# HANDS_FREE_ControlUnit_V2.net
KiCad netlist of a schematic drawn in Altium Designer
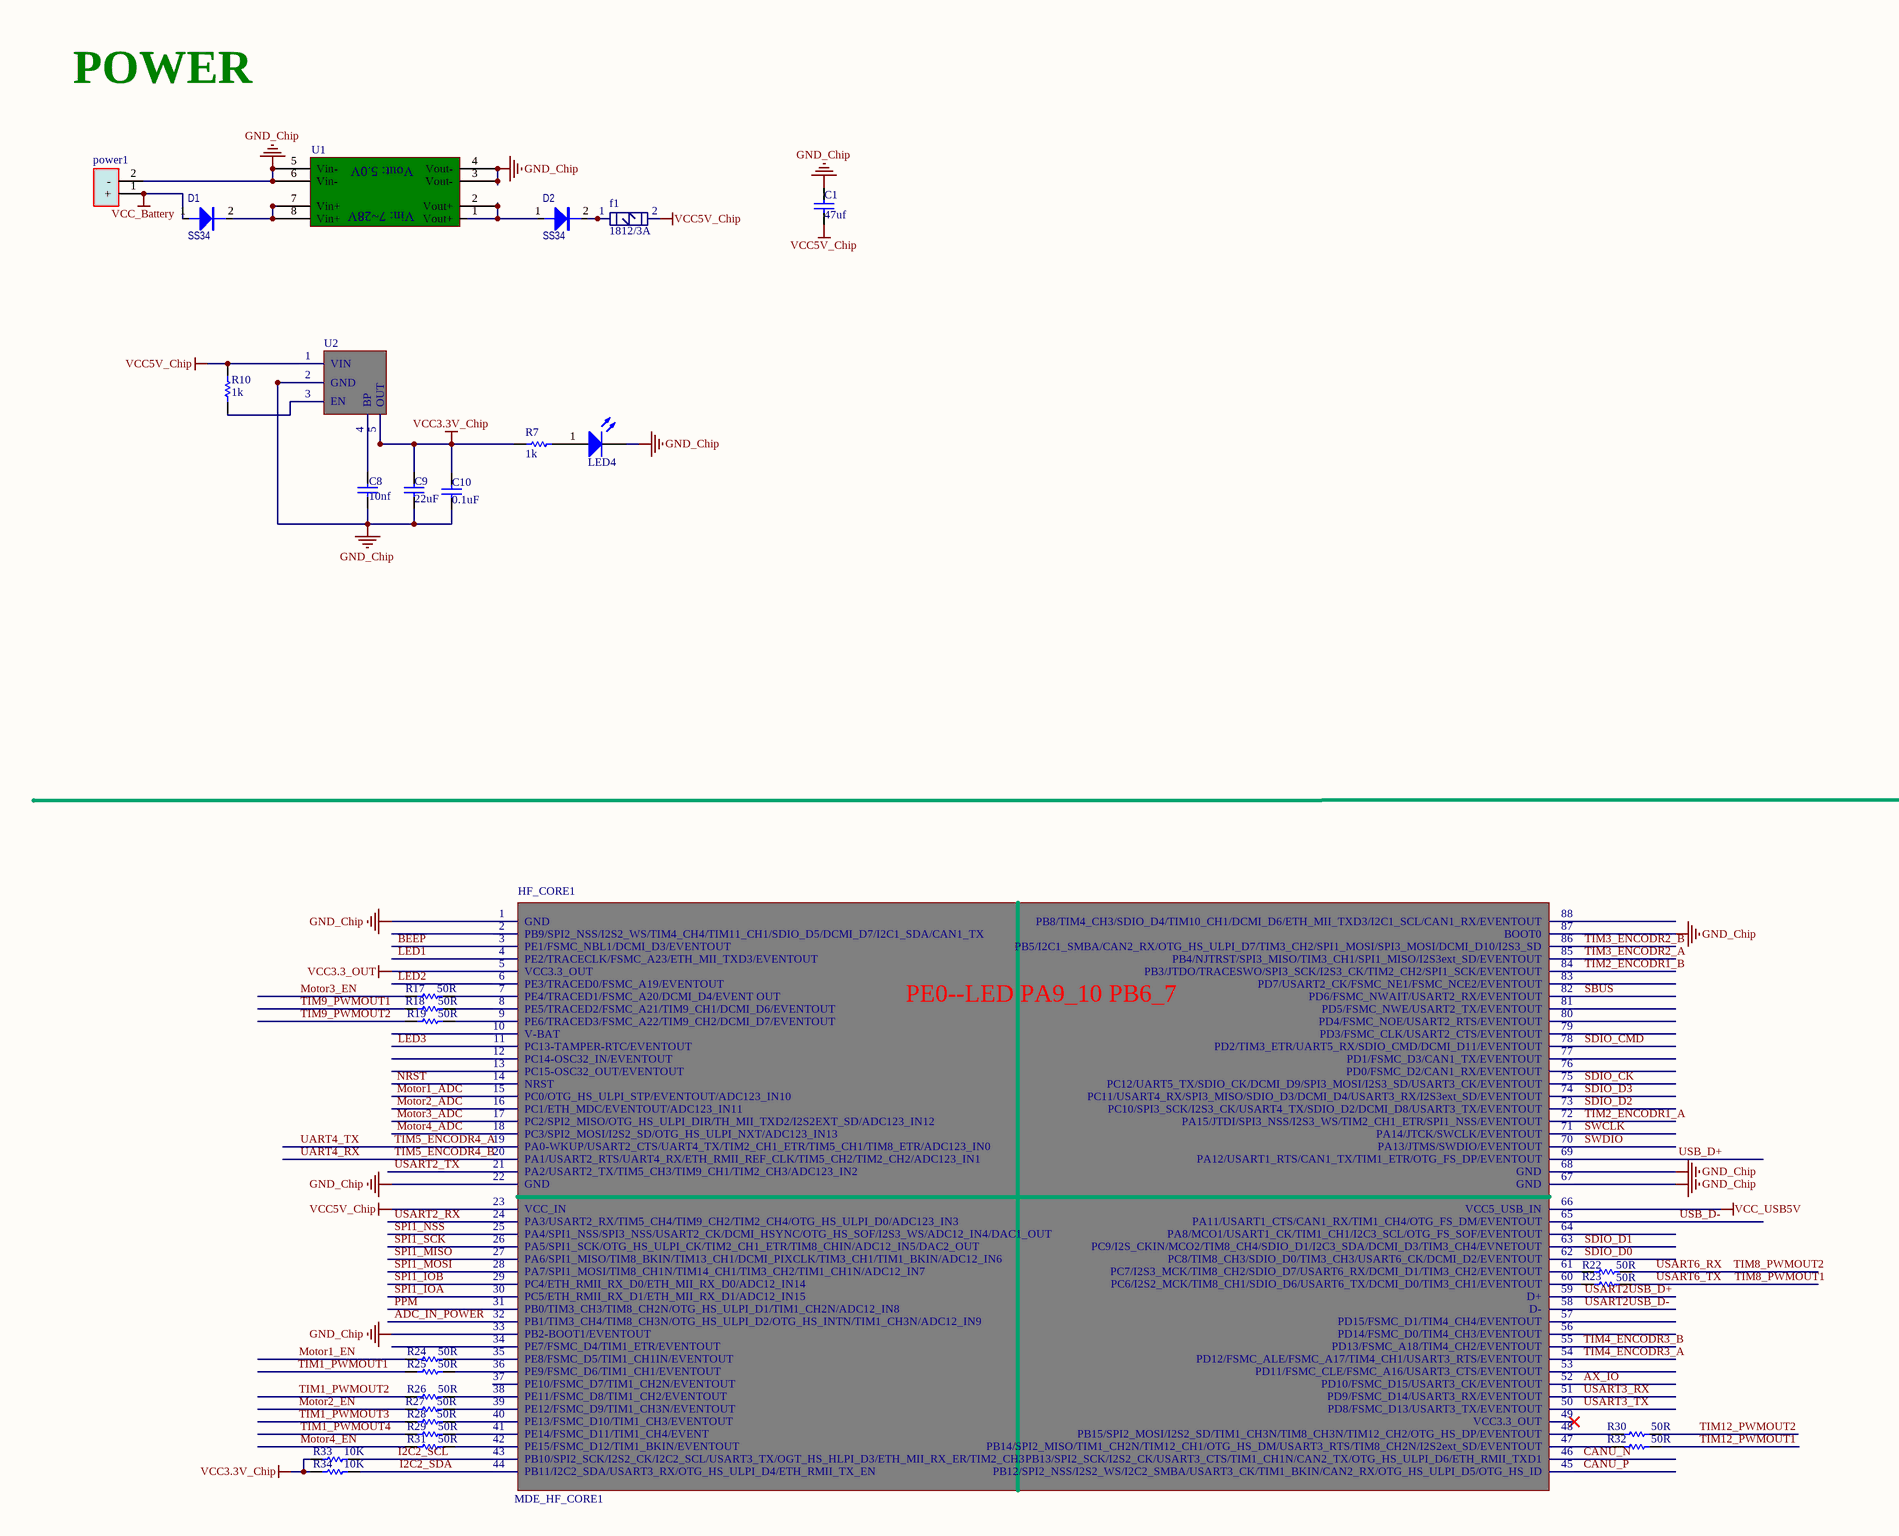
[diagram p0: HANDS_FREE_ControlUnit_V2.SchDoc, top left]
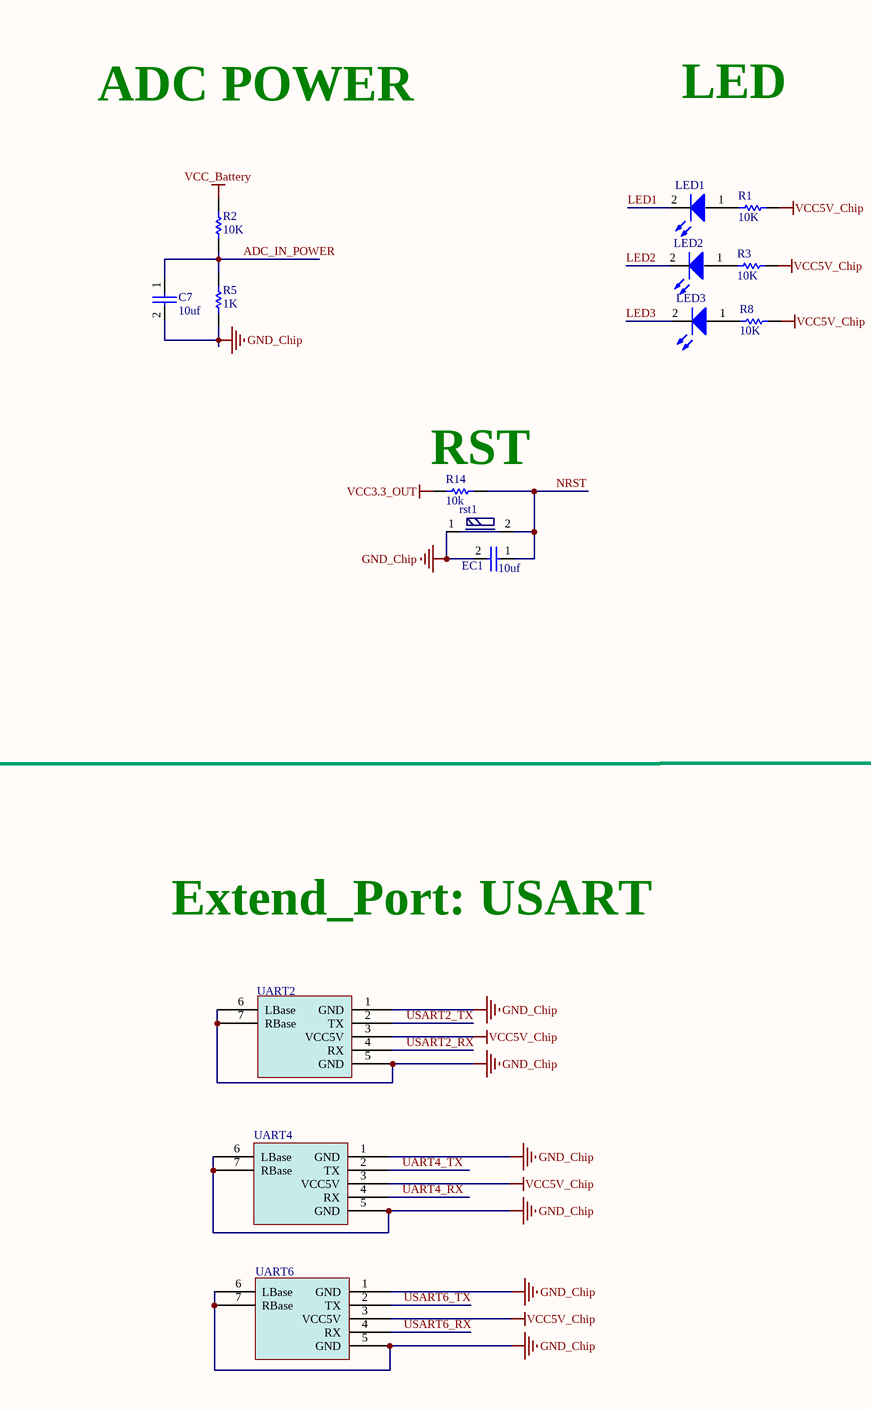
[diagram p1: HANDS_FREE_ControlUnit_V2.SchDoc, top middle]
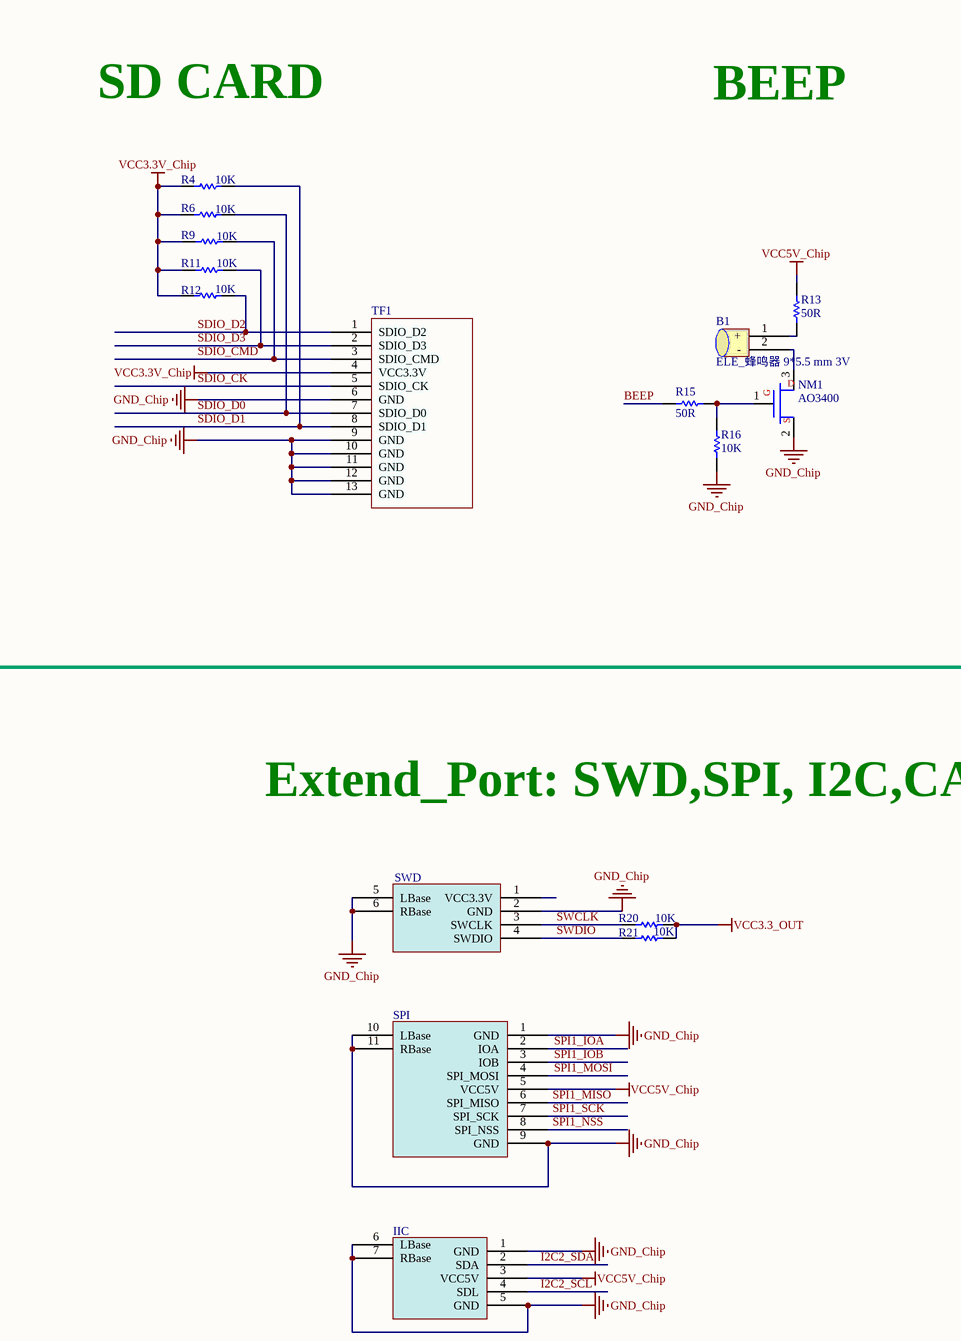
[diagram p2: HANDS_FREE_ControlUnit_V2.SchDoc, top right]
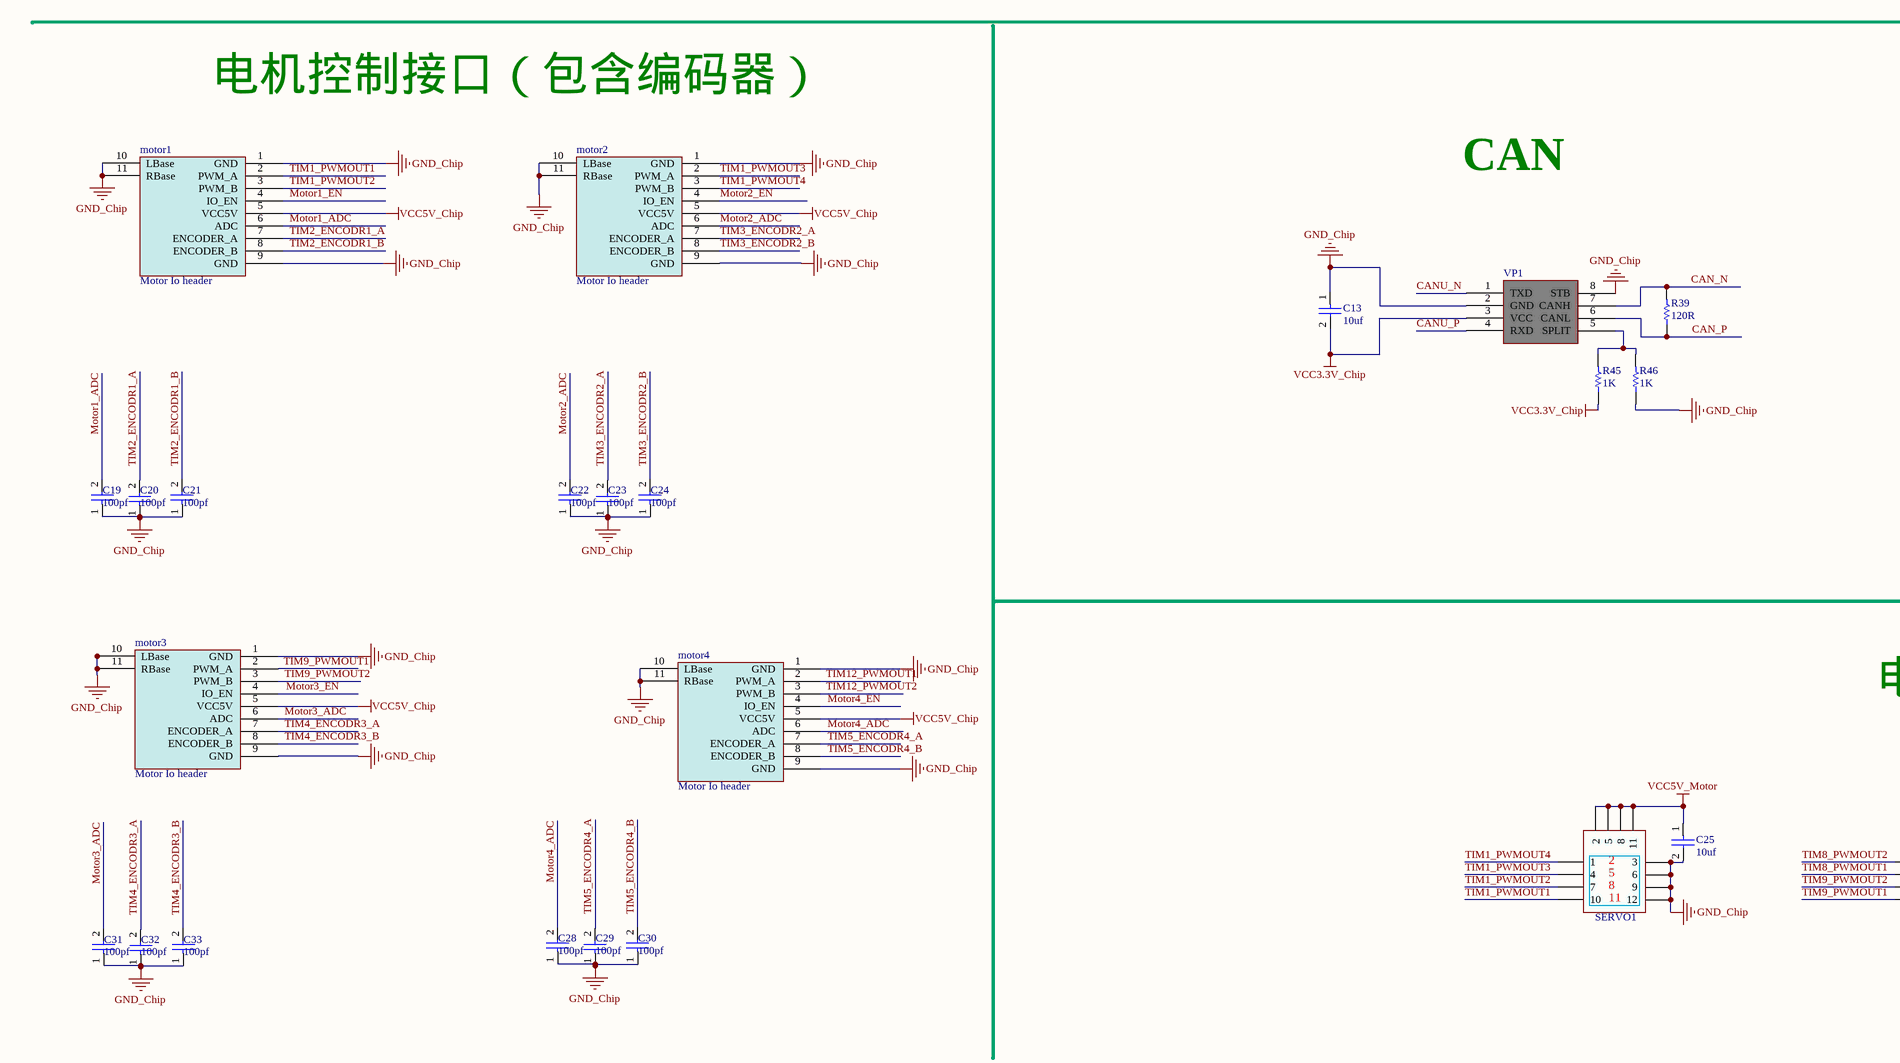
[diagram p3: HANDS_FREE_ControlUnit_V2.SchDoc, bottom left]
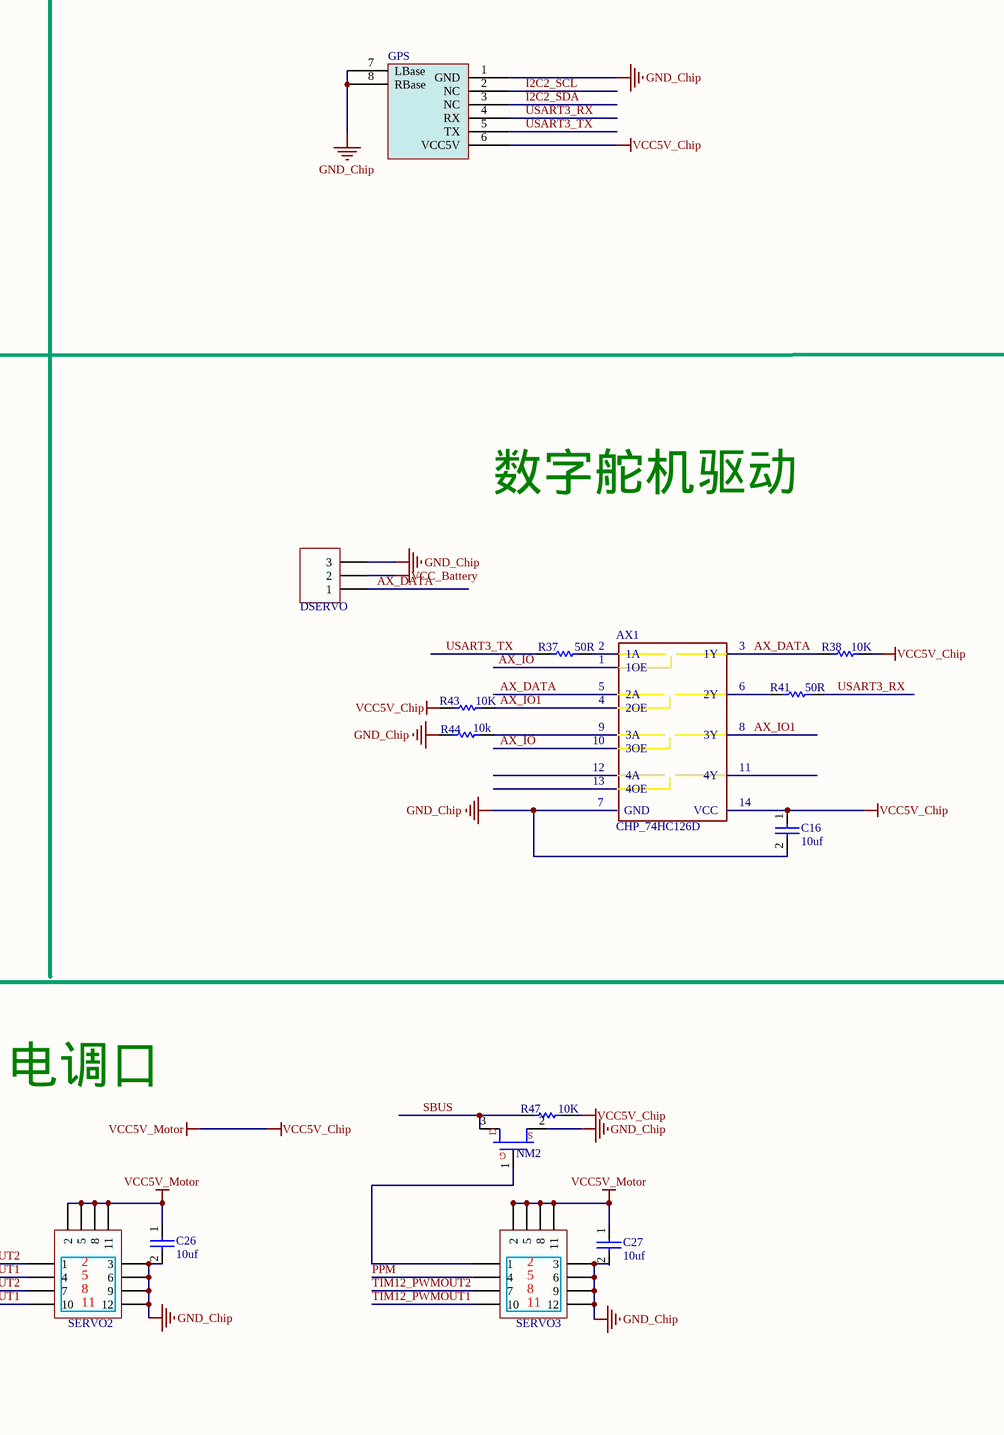
[diagram p4: HANDS_FREE_ControlUnit_V2.SchDoc, bottom middle]
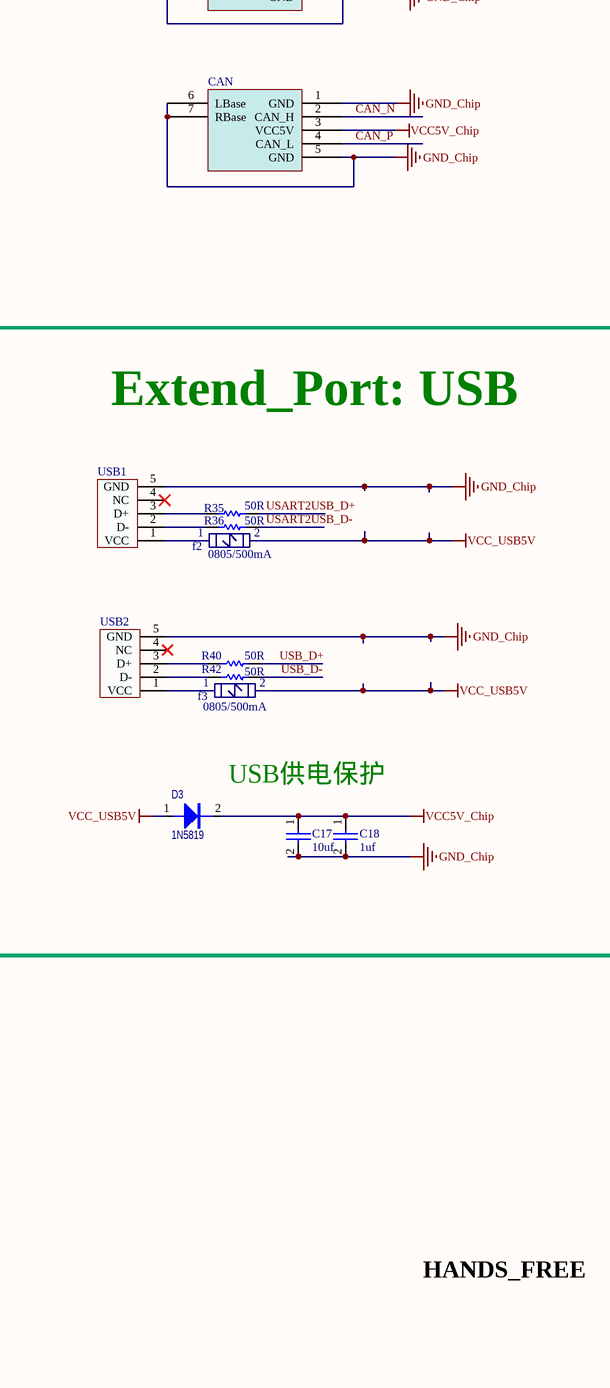
[diagram p5: HANDS_FREE_ControlUnit_V2.SchDoc, bottom right]

(export (version "E")
  (design (tool "Eeschema 10.0.6"))
  (components
    (comp (ref "AX1")
      (value "CHP_74HC126D")
      (footprint "CHP_SOP_14P")
      (description "4路三态门缓冲器")
      (libsource (lib "HANDS-FREEE-PcbLib-V1.01") (part "CHP_74HC126D"))
    )
    (comp (ref "B1")
      (value "ELE_蜂鸣器 9*5.5 mm 3V")
      (footprint "ELE_蜂鸣器_D_9*5.5")
      (description "直插 蜂鸣器 9mm")
      (libsource (lib "Hands_free") (part "ELE_蜂鸣器 9*5.5 mm 3V"))
    )
    (comp (ref "C1") (value "47uf") (footprint "ELE_1206_P") (libsource (lib "My lib") (part "Cap")))
    (comp (ref "C7")
      (value "10uf")
      (footprint "ELE_0603_P")
      (description "贴片 电容100pf 0603")
      (libsource (lib "Hands_free") (part "ELE_Standard_Cap100pf"))
    )
    (comp (ref "C8") (value "10nf") (footprint "ELE_0603_P") (libsource (lib "My lib") (part "Cap")))
    (comp (ref "C9") (value "22uF") (footprint "ELE_0603_P") (libsource (lib "My lib") (part "Cap")))
    (comp (ref "C10") (value "0.1uF") (footprint "ELE_0603_P") (libsource (lib "My lib") (part "Cap")))
    (comp (ref "C13")
      (value "10uf")
      (footprint "ELE_0603_P")
      (description "贴片 电容10uf 0603")
      (libsource (lib "Hands_free") (part "ELE_Standard_Cap10uf"))
    )
    (comp (ref "C16")
      (value "10uf")
      (footprint "ELE_0603_P")
      (description "贴片 电容10uf 0603")
      (libsource (lib "Hands_free") (part "ELE_Standard_Cap10uf"))
    )
    (comp (ref "C17")
      (value "10uf")
      (footprint "ELE_0603_P")
      (description "贴片 电容10uf 0603")
      (libsource (lib "Hands_free") (part "ELE_Standard_Cap10uf"))
    )
    (comp (ref "C18")
      (value "1uf")
      (footprint "ELE_0603_P")
      (description "贴片 电容1uf 0603")
      (libsource (lib "Hands_free") (part "ELE_Standard_Cap1uf"))
    )
    (comp (ref "C19")
      (value "100pf")
      (footprint "ELE_0603_P")
      (description "贴片 电容100pf 0603")
      (libsource (lib "Hands_free") (part "ELE_Standard_Cap100pf"))
    )
    (comp (ref "C20")
      (value "100pf")
      (footprint "ELE_0603_P")
      (description "贴片 电容100pf 0603")
      (libsource (lib "Hands_free") (part "ELE_Standard_Cap100pf"))
    )
    (comp (ref "C21")
      (value "100pf")
      (footprint "ELE_0603_P")
      (description "贴片 电容100pf 0603")
      (libsource (lib "Hands_free") (part "ELE_Standard_Cap100pf"))
    )
    (comp (ref "C22")
      (value "100pf")
      (footprint "ELE_0603_P")
      (description "贴片 电容100pf 0603")
      (libsource (lib "Hands_free") (part "ELE_Standard_Cap100pf"))
    )
    (comp (ref "C23")
      (value "100pf")
      (footprint "ELE_0603_P")
      (description "贴片 电容100pf 0603")
      (libsource (lib "Hands_free") (part "ELE_Standard_Cap100pf"))
    )
    (comp (ref "C24")
      (value "100pf")
      (footprint "ELE_0603_P")
      (description "贴片 电容100pf 0603")
      (libsource (lib "Hands_free") (part "ELE_Standard_Cap100pf"))
    )
    (comp (ref "C25")
      (value "10uf")
      (footprint "ELE_0603_P")
      (description "贴片 电容10uf 0603")
      (libsource (lib "Hands_free") (part "ELE_Standard_Cap10uf"))
    )
    (comp (ref "C26")
      (value "10uf")
      (footprint "ELE_0603_P")
      (description "贴片 电容10uf 0603")
      (libsource (lib "Hands_free") (part "ELE_Standard_Cap10uf"))
    )
    (comp (ref "C27")
      (value "10uf")
      (footprint "ELE_0603_P")
      (description "贴片 电容10uf 0603")
      (libsource (lib "Hands_free") (part "ELE_Standard_Cap10uf"))
    )
    (comp (ref "C28")
      (value "100pf")
      (footprint "ELE_0603_P")
      (description "贴片 电容100pf 0603")
      (libsource (lib "Hands_free") (part "ELE_Standard_Cap100pf"))
    )
    (comp (ref "C29")
      (value "100pf")
      (footprint "ELE_0603_P")
      (description "贴片 电容100pf 0603")
      (libsource (lib "Hands_free") (part "ELE_Standard_Cap100pf"))
    )
    (comp (ref "C30")
      (value "100pf")
      (footprint "ELE_0603_P")
      (description "贴片 电容100pf 0603")
      (libsource (lib "Hands_free") (part "ELE_Standard_Cap100pf"))
    )
    (comp (ref "C31")
      (value "100pf")
      (footprint "ELE_0603_P")
      (description "贴片 电容100pf 0603")
      (libsource (lib "Hands_free") (part "ELE_Standard_Cap100pf"))
    )
    (comp (ref "C32")
      (value "100pf")
      (footprint "ELE_0603_P")
      (description "贴片 电容100pf 0603")
      (libsource (lib "Hands_free") (part "ELE_Standard_Cap100pf"))
    )
    (comp (ref "C33")
      (value "100pf")
      (footprint "ELE_0603_P")
      (description "贴片 电容100pf 0603")
      (libsource (lib "Hands_free") (part "ELE_Standard_Cap100pf"))
    )
    (comp (ref "CAN")
      (value "HANDS_FREE_IMU")
      (footprint "HDR_Molex_PH_1.25_5P")
      (libsource (lib "Hands_free") (part "HANDS_FREE_IMU"))
    )
    (comp (ref "D1")
      (value "SS34")
      (footprint "ELE_D1206")
      (description "贴片 二极管 SS34/SS54")
      (libsource (lib "Hands_free") (part "ELE_Standard_Diode_1206"))
    )
    (comp (ref "D2")
      (value "SS34")
      (footprint "ELE_D1206")
      (description "贴片 二极管 SS34/SS54")
      (libsource (lib "Hands_free") (part "ELE_Standard_Diode_1206"))
    )
    (comp (ref "D3")
      (value "1N5819")
      (footprint "ELE_SOD-323")
      (description "贴片 二极管 SOD323")
      (libsource (lib "Hands_free") (part "ELE_Standard_Diode_SOD323"))
    )
    (comp (ref "DSERVO")
      (value "HDR_Header_1*3")
      (footprint "HDR_数字舵机接口_D")
      (fields (field (name "PUBLISHER") "Altium Limited"))
      (libsource (lib "Hands_free") (part "HDR_Header_1*3"))
    )
    (comp (ref "EC1")
      (value "10uf")
      (footprint "ELE_0603_P")
      (description "贴片 电容100pf 0603")
      (libsource (lib "Hands_free") (part "ELE_Standard_Cap100pf"))
    )
    (comp (ref "f1")
      (value "1812/3A")
      (footprint "ELE_FUZE_1812")
      (description "贴片保险丝 1812 3A")
      (libsource (lib "Hands_free") (part "ELE_Standard_Fuze_1812/3A"))
    )
    (comp (ref "f2")
      (value "0805/500mA")
      (footprint "ELE_FUZE_0805")
      (description "贴片保险丝 0805 500mA")
      (libsource (lib "Hands_free") (part "ELE_Standard_Fuze_0805/500mA"))
    )
    (comp (ref "f3")
      (value "0805/500mA")
      (footprint "ELE_FUZE_0805")
      (description "贴片保险丝 0805 500mA")
      (libsource (lib "Hands_free") (part "ELE_Standard_Fuze_0805/500mA"))
    )
    (comp (ref "GPS")
      (value "HANDS_FREE_GPS")
      (footprint "HDR_Molex_PH_1.25_6P")
      (libsource (lib "Hands_free") (part "HANDS_FREE_GPS"))
    )
    (comp (ref "HF_CORE1")
      (value "MDE_HF_CORE1")
      (footprint "MDE_HF_CORE1")
      (description "HANDS FREE核心板1代")
      (libsource (lib "HANDS-FREEE-PcbLib-V1.11") (part "MDE_HF_CORE1"))
    )
    (comp (ref "IIC")
      (value "HANDS_FREE_IIC")
      (footprint "HDR_Molex_PH_1.25_5P")
      (libsource (lib "Hands_free") (part "HANDS_FREE_IIC"))
    )
    (comp (ref "LED1")
      (value "ELE_LED")
      (footprint "ELE_0603极性_P")
      (description "发光二极管 0603")
      (fields (field (name "PUBLISHER") "Altium Limited"))
      (libsource (lib "HANDS-FREEE-PcbLib-V1.11") (part "ELE_LED"))
    )
    (comp (ref "LED2")
      (value "ELE_LED")
      (footprint "ELE_0603极性_P")
      (description "发光二极管 0603")
      (fields (field (name "PUBLISHER") "Altium Limited"))
      (libsource (lib "HANDS-FREEE-PcbLib-V1.11") (part "ELE_LED"))
    )
    (comp (ref "LED3")
      (value "ELE_LED")
      (footprint "ELE_0603极性_P")
      (description "发光二极管 0603")
      (fields (field (name "PUBLISHER") "Altium Limited"))
      (libsource (lib "HANDS-FREEE-PcbLib-V1.11") (part "ELE_LED"))
    )
    (comp (ref "LED4") (value "Led_sp") (footprint "ELE_0603极性_P") (libsource (lib "My lib") (part "Led_sp")))
    (comp (ref "motor1")
      (value "Motor Io header")
      (footprint "HDR_Molex_PH_1.25_9P")
      (description "卧贴 molex 1.25间距 9P接口")
      (libsource (lib "Hands_free") (part "HANDS_FREE_MOTOR"))
    )
    (comp (ref "motor2")
      (value "Motor Io header")
      (footprint "HDR_Molex_PH_1.25_9P")
      (description "卧贴 molex 1.25间距 9P接口")
      (libsource (lib "Hands_free") (part "HANDS_FREE_MOTOR"))
    )
    (comp (ref "motor3")
      (value "Motor Io header")
      (footprint "HDR_Molex_PH_1.25_9P")
      (description "卧贴 molex 1.25间距 9P接口")
      (libsource (lib "Hands_free") (part "HANDS_FREE_MOTOR"))
    )
    (comp (ref "motor4")
      (value "Motor Io header")
      (footprint "HDR_Molex_PH_1.25_9P")
      (description "卧贴 molex 1.25间距 9P接口")
      (libsource (lib "Hands_free") (part "HANDS_FREE_MOTOR"))
    )
    (comp (ref "NM1")
      (value "AO3400")
      (footprint "CHP_SOT23_P_3P")
      (description "贴片 NMOS管 SOT23")
      (fields (field (name "PUBLISHER") "Altium Limited"))
      (libsource (lib "Hands_free") (part "ELE_NMOS_1"))
    )
    (comp (ref "NM2")
      (value "AO3400")
      (footprint "CHP_SOT23_P_3P")
      (description "贴片 NMOS管 SOT23")
      (fields (field (name "PUBLISHER") "Altium Limited"))
      (libsource (lib "Hands_free") (part "ELE_NMOS_1"))
    )
    (comp (ref "power1")
      (value "HDR_Header_Power_2P")
      (footprint "HDR_MOLEX_CANMX3.0_DH_2P")
      (libsource (lib "HANDS-FREEE-PcbLib-V1.00") (part "HDR_Header_Power_2P"))
    )
    (comp (ref "R1")
      (value "10K")
      (footprint "ELE_0603_P")
      (description "贴片 电阻1K欧 0603")
      (libsource (lib "Hands_free") (part "ELE_Standard_R1K"))
    )
    (comp (ref "R2")
      (value "10K")
      (footprint "ELE_0603_P")
      (description "贴片 电阻1K欧 0603")
      (libsource (lib "Hands_free") (part "ELE_Standard_R1K"))
    )
    (comp (ref "R3")
      (value "10K")
      (footprint "ELE_0603_P")
      (description "贴片 电阻1K欧 0603")
      (libsource (lib "Hands_free") (part "ELE_Standard_R1K"))
    )
    (comp (ref "R4")
      (value "10K")
      (footprint "ELE_0603_P")
      (description "贴片 电阻10K欧 0603")
      (libsource (lib "Hands_free") (part "ELE_Standard_R10K"))
    )
    (comp (ref "R5")
      (value "1K")
      (footprint "ELE_0603_P")
      (description "贴片 电阻10K欧 0603")
      (libsource (lib "Hands_free") (part "ELE_Standard_R10K"))
    )
    (comp (ref "R6")
      (value "10K")
      (footprint "ELE_0603_P")
      (description "贴片 电阻10K欧 0603")
      (libsource (lib "Hands_free") (part "ELE_Standard_R10K"))
    )
    (comp (ref "R7")
      (value "1k")
      (footprint "ELE_0603_P")
      (description "贴片 电阻50欧 0603")
      (libsource (lib "Hands_free") (part "ELE_Standard_R50R"))
    )
    (comp (ref "R8")
      (value "10K")
      (footprint "ELE_0603_P")
      (description "贴片 电阻1K欧 0603")
      (libsource (lib "Hands_free") (part "ELE_Standard_R1K"))
    )
    (comp (ref "R9")
      (value "10K")
      (footprint "ELE_0603_P")
      (description "贴片 电阻10K欧 0603")
      (libsource (lib "Hands_free") (part "ELE_Standard_R10K"))
    )
    (comp (ref "R10")
      (value "1k")
      (footprint "ELE_0603_P")
      (description "贴片 电阻50欧 0603")
      (libsource (lib "Hands_free") (part "ELE_Standard_R50R"))
    )
    (comp (ref "R11")
      (value "10K")
      (footprint "ELE_0603_P")
      (description "贴片 电阻10K欧 0603")
      (libsource (lib "Hands_free") (part "ELE_Standard_R10K"))
    )
    (comp (ref "R12")
      (value "10K")
      (footprint "ELE_0603_P")
      (description "贴片 电阻10K欧 0603")
      (libsource (lib "Hands_free") (part "ELE_Standard_R10K"))
    )
    (comp (ref "R13")
      (value "50R")
      (footprint "ELE_0603_P")
      (description "贴片 电阻10K欧 0603")
      (libsource (lib "Hands_free") (part "ELE_Standard_R10K"))
    )
    (comp (ref "R14")
      (value "10k")
      (footprint "ELE_0603_P")
      (description "贴片 电阻50欧 0603")
      (libsource (lib "Hands_free") (part "ELE_Standard_R50R"))
    )
    (comp (ref "R15")
      (value "50R")
      (footprint "ELE_0603_P")
      (description "贴片 电阻50欧 0603")
      (libsource (lib "Hands_free") (part "ELE_Standard_R50R"))
    )
    (comp (ref "R16")
      (value "10K")
      (footprint "ELE_0603_P")
      (description "贴片 电阻10K欧 0603")
      (libsource (lib "Hands_free") (part "ELE_Standard_R10K"))
    )
    (comp (ref "R17")
      (value "50R")
      (footprint "ELE_0603_P")
      (description "贴片 电阻50欧 0603")
      (libsource (lib "Hands_free") (part "ELE_Standard_R50R"))
    )
    (comp (ref "R18")
      (value "50R")
      (footprint "ELE_0603_P")
      (description "贴片 电阻50欧 0603")
      (libsource (lib "Hands_free") (part "ELE_Standard_R50R"))
    )
    (comp (ref "R19")
      (value "50R")
      (footprint "ELE_0603_P")
      (description "贴片 电阻50欧 0603")
      (libsource (lib "Hands_free") (part "ELE_Standard_R50R"))
    )
    (comp (ref "R20")
      (value "10K")
      (footprint "ELE_0603_P")
      (description "贴片 电阻10K欧 0603")
      (libsource (lib "Hands_free") (part "ELE_Standard_R10K"))
    )
    (comp (ref "R21")
      (value "10K")
      (footprint "ELE_0603_P")
      (description "贴片 电阻10K欧 0603")
      (libsource (lib "Hands_free") (part "ELE_Standard_R10K"))
    )
    (comp (ref "R22")
      (value "50R")
      (footprint "ELE_0603_P")
      (description "贴片 电阻50欧 0603")
      (libsource (lib "Hands_free") (part "ELE_Standard_R50R"))
    )
    (comp (ref "R23")
      (value "50R")
      (footprint "ELE_0603_P")
      (description "贴片 电阻50欧 0603")
      (libsource (lib "Hands_free") (part "ELE_Standard_R50R"))
    )
    (comp (ref "R24")
      (value "50R")
      (footprint "ELE_0603_P")
      (description "贴片 电阻50欧 0603")
      (libsource (lib "Hands_free") (part "ELE_Standard_R50R"))
    )
    (comp (ref "R25")
      (value "50R")
      (footprint "ELE_0603_P")
      (description "贴片 电阻50欧 0603")
      (libsource (lib "Hands_free") (part "ELE_Standard_R50R"))
    )
    (comp (ref "R26")
      (value "50R")
      (footprint "ELE_0603_P")
      (description "贴片 电阻50欧 0603")
      (libsource (lib "Hands_free") (part "ELE_Standard_R50R"))
    )
    (comp (ref "R27")
      (value "50R")
      (footprint "ELE_0603_P")
      (description "贴片 电阻50欧 0603")
      (libsource (lib "Hands_free") (part "ELE_Standard_R50R"))
    )
    (comp (ref "R28")
      (value "50R")
      (footprint "ELE_0603_P")
      (description "贴片 电阻50欧 0603")
      (libsource (lib "Hands_free") (part "ELE_Standard_R50R"))
    )
    (comp (ref "R29")
      (value "50R")
      (footprint "ELE_0603_P")
      (description "贴片 电阻50欧 0603")
      (libsource (lib "Hands_free") (part "ELE_Standard_R50R"))
    )
    (comp (ref "R30")
      (value "50R")
      (footprint "ELE_0603_P")
      (description "贴片 电阻50欧 0603")
      (libsource (lib "Hands_free") (part "ELE_Standard_R50R"))
    )
    (comp (ref "R31")
      (value "50R")
      (footprint "ELE_0603_P")
      (description "贴片 电阻50欧 0603")
      (libsource (lib "Hands_free") (part "ELE_Standard_R50R"))
    )
    (comp (ref "R32")
      (value "50R")
      (footprint "ELE_0603_P")
      (description "贴片 电阻50欧 0603")
      (libsource (lib "Hands_free") (part "ELE_Standard_R50R"))
    )
    (comp (ref "R33")
      (value "10K")
      (footprint "ELE_0603_P")
      (description "贴片 电阻10K欧 0603")
      (libsource (lib "Hands_free") (part "ELE_Standard_R10K"))
    )
    (comp (ref "R34")
      (value "10K")
      (footprint "ELE_0603_P")
      (description "贴片 电阻10K欧 0603")
      (libsource (lib "Hands_free") (part "ELE_Standard_R10K"))
    )
    (comp (ref "R35")
      (value "50R")
      (footprint "ELE_0603_P")
      (description "贴片 电阻50欧 0603")
      (libsource (lib "Hands_free") (part "ELE_Standard_R50R"))
    )
    (comp (ref "R36")
      (value "50R")
      (footprint "ELE_0603_P")
      (description "贴片 电阻50欧 0603")
      (libsource (lib "Hands_free") (part "ELE_Standard_R50R"))
    )
    (comp (ref "R37")
      (value "50R")
      (footprint "ELE_0603_P")
      (description "贴片 电阻50欧 0603")
      (libsource (lib "Hands_free") (part "ELE_Standard_R50R"))
    )
    (comp (ref "R38")
      (value "10K")
      (footprint "ELE_0603_P")
      (description "贴片 电阻10K欧 0603")
      (libsource (lib "Hands_free") (part "10K"))
    )
    (comp (ref "R39")
      (value "120R")
      (footprint "ELE_0603_P")
      (description "贴片 电阻120欧 0603")
      (libsource (lib "Hands_free") (part "ELE_Standard_R120R"))
    )
    (comp (ref "R40")
      (value "50R")
      (footprint "ELE_0603_P")
      (description "贴片 电阻50欧 0603")
      (libsource (lib "Hands_free") (part "ELE_Standard_R50R"))
    )
    (comp (ref "R41")
      (value "50R")
      (footprint "ELE_0603_P")
      (description "贴片 电阻50欧 0603")
      (libsource (lib "Hands_free") (part "ELE_Standard_R50R"))
    )
    (comp (ref "R42")
      (value "50R")
      (footprint "ELE_0603_P")
      (description "贴片 电阻50欧 0603")
      (libsource (lib "Hands_free") (part "ELE_Standard_R50R"))
    )
    (comp (ref "R43")
      (value "10K")
      (footprint "ELE_0603_P")
      (description "贴片 电阻50欧 0603")
      (libsource (lib "Hands_free") (part "ELE_Standard_R50R"))
    )
    (comp (ref "R44")
      (value "10k")
      (footprint "ELE_0603_P")
      (description "贴片 电阻50欧 0603")
      (libsource (lib "Hands_free") (part "ELE_Standard_R50R"))
    )
    (comp (ref "R45")
      (value "1K")
      (footprint "ELE_0603_P")
      (description "贴片 电阻10K欧 0603")
      (libsource (lib "Hands_free") (part "ELE_Standard_R10K"))
    )
    (comp (ref "R46")
      (value "1K")
      (footprint "ELE_0603_P")
      (description "贴片 电阻10K欧 0603")
      (libsource (lib "Hands_free") (part "ELE_Standard_R10K"))
    )
    (comp (ref "R47")
      (value "10K")
      (footprint "ELE_0603_P")
      (description "贴片 电阻10K欧 0603")
      (libsource (lib "Hands_free") (part "ELE_Standard_R10K"))
    )
    (comp (ref "rst1")
      (value "ELE_KEY_1")
      (footprint "ELE_KEY_P")
      (description "贴片 触发开关 2P")
      (libsource (lib "Hands_free") (part "ELE_KEY_1"))
    )
    (comp (ref "SERVO1")
      (value "HDR_Header_4*3")
      (footprint "HDR_Header_2.54/3.0_DV_3*4")
      (description "直插 三排排针")
      (libsource (lib "Hands_free") (part "HDR_Header_4*3"))
    )
    (comp (ref "SERVO2")
      (value "HDR_Header_4*3")
      (footprint "HDR_Header_2.54/3.0_DV_3*4")
      (description "直插 三排排针")
      (libsource (lib "Hands_free") (part "HDR_Header_4*3"))
    )
    (comp (ref "SERVO3")
      (value "HDR_Header_4*3")
      (footprint "HDR_Header_2.54/3.0_DV_3*4")
      (description "直插 三排排针")
      (libsource (lib "Hands_free") (part "HDR_Header_4*3"))
    )
    (comp (ref "SPI")
      (value "HANDS_FREE_SPI")
      (footprint "HDR_Molex_PH_1.25_9P")
      (libsource (lib "Hands_free") (part "HANDS_FREE_SPI"))
    )
    (comp (ref "SWD")
      (value "HANDS_FREE_SWD")
      (footprint "HDR_Molex_PH_1.25_4P")
      (libsource (lib "Hands_free") (part "HANDS_FREE_SWD"))
    )
    (comp (ref "TF1")
      (value "HDR_MicroTFCARD")
      (footprint "HDR_TFCARD_P")
      (libsource (lib "Hands_free") (part "HDR_MicroTFCARD"))
    )
    (comp (ref "U1")
      (value "MDE_DM02-5.0")
      (footprint "MDE_DM02-5.0")
      (libsource (lib "Hands_free") (part "MDE_DM02-5.0"))
    )
    (comp (ref "U2")
      (value "~")
      (footprint "CHP_SOT23_P_5P")
      (description "贴片 RT9193稳压芯片 SOT23_5P 3.3v")
      (libsource (lib "Hands_free") (part "CHP_RT9193"))
    )
    (comp (ref "UART2")
      (value "HANDS_FREE_USART")
      (footprint "HDR_Molex_PH_1.25_5P")
      (libsource (lib "Hands_free") (part "HANDS_FREE_USART"))
    )
    (comp (ref "UART4")
      (value "HANDS_FREE_USART")
      (footprint "HDR_Molex_PH_1.25_5P")
      (libsource (lib "Hands_free") (part "HANDS_FREE_USART"))
    )
    (comp (ref "UART6")
      (value "HANDS_FREE_USART")
      (footprint "HDR_Molex_PH_1.25_5P")
      (libsource (lib "Hands_free") (part "HANDS_FREE_USART"))
    )
    (comp (ref "USB1")
      (value "USBMICRO")
      (footprint "HDR_USB_Micro2")
      (libsource (lib "Hands_free") (part "HDR_USBMINI"))
    )
    (comp (ref "USB2")
      (value "USBMICRO")
      (footprint "HDR_USB_Micro2")
      (libsource (lib "Hands_free") (part "HDR_USBMINI"))
    )
    (comp (ref "VP1")
      (value "CHP_VP230_P")
      (footprint "CHP_VP230_P")
      (libsource (lib "Hands_free") (part "CHP_VP230_P"))
    )
  )
  (nets
    (net (code "1") (name "/ADC_IN_POWER") (class "Default")
      (node (ref "C7") (pin "1") (pintype "passive"))
      (node (ref "HF_CORE1") (pin "32") (pinfunction "PB1/TIM3_CH4/TIM8_CH3N/OTG_HS_ULPI_D2/OTG_HS_INTN/TIM1_CH3N/ADC12_IN9_32") (pintype "passive"))
      (node (ref "R2") (pin "2") (pinfunction "2_2") (pintype "passive"))
      (node (ref "R5") (pin "1") (pinfunction "1_1") (pintype "passive"))
    )
    (net (code "2") (name "/AX_DATA") (class "Default")
      (node (ref "AX1") (pin "3") (pinfunction "1Y_3") (pintype "passive"))
      (node (ref "AX1") (pin "5") (pinfunction "2A_5") (pintype "passive"))
      (node (ref "DSERVO") (pin "1") (pinfunction "1_1") (pintype "passive"))
      (node (ref "R38") (pin "2") (pinfunction "2_2") (pintype "passive"))
    )
    (net (code "3") (name "/AX_IO") (class "Default")
      (node (ref "AX1") (pin "1") (pinfunction "1OE_1") (pintype "passive"))
      (node (ref "AX1") (pin "10") (pinfunction "3OE_10") (pintype "passive"))
      (node (ref "HF_CORE1") (pin "52") (pinfunction "PD10/FSMC_D15/USART3_CK/EVENTOUT_52") (pintype "passive"))
    )
    (net (code "4") (name "/AX_IO1") (class "Default")
      (node (ref "AX1") (pin "4") (pinfunction "2OE_4") (pintype "passive"))
      (node (ref "AX1") (pin "8") (pinfunction "3Y_8") (pintype "passive"))
      (node (ref "R43") (pin "1") (pinfunction "1_1") (pintype "passive"))
    )
    (net (code "5") (name "/BEEP") (class "Default")
      (node (ref "HF_CORE1") (pin "3") (pinfunction "PE1/FSMC_NBL1/DCMI_D3/EVENTOUT_3") (pintype "passive"))
      (node (ref "R15") (pin "2") (pinfunction "2_2") (pintype "passive"))
    )
    (net (code "6") (name "/CANU_N") (class "Default")
      (node (ref "HF_CORE1") (pin "46") (pinfunction "PB13/SPI2_SCK/I2S2_CK/USART3_CTS/TIM1_CH1N/CAN2_TX/OTG_HS_ULPI_D6/ETH_RMII_TXD1_46") (pintype "passive"))
      (node (ref "VP1") (pin "1") (pinfunction "TXD_1") (pintype "passive"))
    )
    (net (code "7") (name "/CANU_P") (class "Default")
      (node (ref "HF_CORE1") (pin "45") (pinfunction "PB12/SPI2_NSS/I2S2_WS/I2C2_SMBA/USART3_CK/TIM1_BKIN/CAN2_RX/OTG_HS_ULPI_D5/OTG_HS_ID_45") (pintype "passive"))
      (node (ref "VP1") (pin "4") (pinfunction "RXD_4") (pintype "passive"))
    )
    (net (code "8") (name "/CAN_N") (class "Default")
      (node (ref "CAN") (pin "2") (pinfunction "CAN_H_2") (pintype "passive"))
      (node (ref "R39") (pin "1") (pinfunction "1_1") (pintype "passive"))
      (node (ref "VP1") (pin "7") (pinfunction "CANH_7") (pintype "passive"))
    )
    (net (code "9") (name "/CAN_P") (class "Default")
      (node (ref "CAN") (pin "4") (pinfunction "CAN_L_4") (pintype "passive"))
      (node (ref "R39") (pin "2") (pinfunction "2_2") (pintype "passive"))
      (node (ref "VP1") (pin "6") (pinfunction "CANL_6") (pintype "passive"))
    )
    (net (code "10") (name "/I2C2_SCL") (class "Default")
      (node (ref "GPS") (pin "2") (pinfunction "NC_2") (pintype "passive"))
      (node (ref "HF_CORE1") (pin "43") (pinfunction "PB10/SPI2_SCK/I2S2_CK/I2C2_SCL/USART3_TX/OGT_HS_HLPI_D3/ETH_MII_RX_ER/TIM2_CH3_43") (pintype "passive"))
      (node (ref "IIC") (pin "4") (pinfunction "SDL_4") (pintype "passive"))
      (node (ref "R33") (pin "1") (pinfunction "1_1") (pintype "passive"))
    )
    (net (code "11") (name "/I2C2_SDA") (class "Default")
      (node (ref "GPS") (pin "3") (pinfunction "NC_3") (pintype "passive"))
      (node (ref "HF_CORE1") (pin "44") (pinfunction "PB11/I2C2_SDA/USART3_RX/OTG_HS_ULPI_D4/ETH_RMII_TX_EN_44") (pintype "passive"))
      (node (ref "IIC") (pin "2") (pinfunction "SDA_2") (pintype "passive"))
      (node (ref "R34") (pin "1") (pinfunction "1_1") (pintype "passive"))
    )
    (net (code "12") (name "/LED1") (class "Default")
      (node (ref "HF_CORE1") (pin "4") (pinfunction "PE2/TRACECLK/FSMC_A23/ETH_MII_TXD3/EVENTOUT_4") (pintype "passive"))
      (node (ref "LED1") (pin "2") (pintype "passive"))
    )
    (net (code "13") (name "/LED2") (class "Default")
      (node (ref "HF_CORE1") (pin "6") (pinfunction "PE3/TRACED0/FSMC_A19/EVENTOUT_6") (pintype "passive"))
      (node (ref "LED2") (pin "2") (pintype "passive"))
    )
    (net (code "14") (name "/LED3") (class "Default")
      (node (ref "HF_CORE1") (pin "11") (pinfunction "PC13-TAMPER-RTC/EVENTOUT_11") (pintype "passive"))
      (node (ref "LED3") (pin "2") (pintype "passive"))
    )
    (net (code "15") (name "/Motor1_ADC") (class "Default")
      (node (ref "C19") (pin "2") (pintype "passive"))
      (node (ref "HF_CORE1") (pin "15") (pinfunction "PC0/OTG_HS_ULPI_STP/EVENTOUT/ADC123_IN10_15") (pintype "passive"))
      (node (ref "motor1") (pin "6") (pinfunction "ADC_6") (pintype "passive"))
    )
    (net (code "16") (name "/Motor1_EN") (class "Default")
      (node (ref "R24") (pin "2") (pinfunction "2_2") (pintype "passive"))
      (node (ref "motor1") (pin "4") (pinfunction "IO_EN_4") (pintype "passive"))
    )
    (net (code "17") (name "/Motor2_ADC") (class "Default")
      (node (ref "C22") (pin "2") (pintype "passive"))
      (node (ref "HF_CORE1") (pin "16") (pinfunction "PC1/ETH_MDC/EVENTOUT/ADC123_IN11_16") (pintype "passive"))
      (node (ref "motor2") (pin "6") (pinfunction "ADC_6") (pintype "passive"))
    )
    (net (code "18") (name "/Motor2_EN") (class "Default")
      (node (ref "R27") (pin "2") (pinfunction "2_2") (pintype "passive"))
      (node (ref "motor2") (pin "4") (pinfunction "IO_EN_4") (pintype "passive"))
    )
    (net (code "19") (name "/Motor3_ADC") (class "Default")
      (node (ref "C31") (pin "2") (pintype "passive"))
      (node (ref "HF_CORE1") (pin "17") (pinfunction "PC2/SPI2_MISO/OTG_HS_ULPI_DIR/TH_MII_TXD2/I2S2EXT_SD/ADC123_IN12_17") (pintype "passive"))
      (node (ref "motor3") (pin "6") (pinfunction "ADC_6") (pintype "passive"))
    )
    (net (code "20") (name "/Motor3_EN") (class "Default")
      (node (ref "R17") (pin "2") (pinfunction "2_2") (pintype "passive"))
      (node (ref "motor3") (pin "4") (pinfunction "IO_EN_4") (pintype "passive"))
    )
    (net (code "21") (name "/Motor4_ADC") (class "Default")
      (node (ref "C28") (pin "2") (pintype "passive"))
      (node (ref "HF_CORE1") (pin "18") (pinfunction "PC3/SPI2_MOSI/I2S2_SD/OTG_HS_ULPI_NXT/ADC123_IN13_18") (pintype "passive"))
      (node (ref "motor4") (pin "6") (pinfunction "ADC_6") (pintype "passive"))
    )
    (net (code "22") (name "/Motor4_EN") (class "Default")
      (node (ref "R31") (pin "2") (pinfunction "2_2") (pintype "passive"))
      (node (ref "motor4") (pin "4") (pinfunction "IO_EN_4") (pintype "passive"))
    )
    (net (code "23") (name "/NRST") (class "Default")
      (node (ref "EC1") (pin "1") (pintype "passive"))
      (node (ref "HF_CORE1") (pin "14") (pinfunction "NRST_14") (pintype "passive"))
      (node (ref "R14") (pin "2") (pinfunction "2_2") (pintype "passive"))
      (node (ref "rst1") (pin "2") (pintype "passive"))
    )
    (net (code "24") (name "/PPM") (class "Default")
      (node (ref "HF_CORE1") (pin "31") (pinfunction "PB0/TIM3_CH3/TIM8_CH2N/OTG_HS_ULPI_D1/TIM1_CH2N/ADC12_IN8_31") (pintype "passive"))
      (node (ref "SERVO3") (pin "4") (pinfunction "4_4") (pintype "passive"))
    )
    (net (code "25") (name "/SBUS") (class "Default")
      (node (ref "HF_CORE1") (pin "82") (pinfunction "PD6/FSMC_NWAIT/USART2_RX/EVENTOUT_82") (pintype "passive"))
      (node (ref "NM2") (pin "3") (pinfunction "D_3") (pintype "passive"))
      (node (ref "R47") (pin "2") (pinfunction "2_2") (pintype "passive"))
    )
    (net (code "26") (name "/SDIO_CK") (class "Default")
      (node (ref "HF_CORE1") (pin "75") (pinfunction "PC12/UART5_TX/SDIO_CK/DCMI_D9/SPI3_MOSI/I2S3_SD/USART3_CK/EVENTOUT_75") (pintype "passive"))
      (node (ref "TF1") (pin "5") (pinfunction "SDIO_CK_5") (pintype "passive"))
    )
    (net (code "27") (name "/SDIO_CMD") (class "Default")
      (node (ref "HF_CORE1") (pin "78") (pinfunction "PD2/TIM3_ETR/UART5_RX/SDIO_CMD/DCMI_D11/EVENTOUT_78") (pintype "passive"))
      (node (ref "R9") (pin "1") (pinfunction "1_1") (pintype "passive"))
      (node (ref "TF1") (pin "3") (pinfunction "SDIO_CMD_3") (pintype "passive"))
    )
    (net (code "28") (name "/SDIO_D0") (class "Default")
      (node (ref "HF_CORE1") (pin "62") (pinfunction "PC8/TIM8_CH3/SDIO_D0/TIM3_CH3/USART6_CK/DCMI_D2/EVENTOUT_62") (pintype "passive"))
      (node (ref "R6") (pin "1") (pinfunction "1_1") (pintype "passive"))
      (node (ref "TF1") (pin "7") (pinfunction "SDIO_D0_7") (pintype "passive"))
    )
    (net (code "29") (name "/SDIO_D1") (class "Default")
      (node (ref "HF_CORE1") (pin "63") (pinfunction "PC9/I2S_CKIN/MCO2/TIM8_CH4/SDIO_D1/I2C3_SDA/DCMI_D3/TIM3_CH4/EVNETOUT_63") (pintype "passive"))
      (node (ref "R4") (pin "1") (pinfunction "1_1") (pintype "passive"))
      (node (ref "TF1") (pin "8") (pinfunction "SDIO_D1_8") (pintype "passive"))
    )
    (net (code "30") (name "/SDIO_D2") (class "Default")
      (node (ref "HF_CORE1") (pin "73") (pinfunction "PC10/SPI3_SCK/I2S3_CK/USART4_TX/SDIO_D2/DCMI_D8/USART3_TX/EVENTOUT_73") (pintype "passive"))
      (node (ref "R12") (pin "1") (pinfunction "1_1") (pintype "passive"))
      (node (ref "TF1") (pin "1") (pinfunction "SDIO_D2_1") (pintype "passive"))
    )
    (net (code "31") (name "/SDIO_D3") (class "Default")
      (node (ref "HF_CORE1") (pin "74") (pinfunction "PC11/USART4_RX/SPI3_MISO/SDIO_D3/DCMI_D4/USART3_RX/I2S3ext_SD/EVENTOUT_74") (pintype "passive"))
      (node (ref "R11") (pin "1") (pinfunction "1_1") (pintype "passive"))
      (node (ref "TF1") (pin "2") (pinfunction "SDIO_D3_2") (pintype "passive"))
    )
    (net (code "32") (name "/SPI1_IOA") (class "Default")
      (node (ref "HF_CORE1") (pin "30") (pinfunction "PC5/ETH_RMII_RX_D1/ETH_MII_RX_D1/ADC12_IN15_30") (pintype "passive"))
      (node (ref "SPI") (pin "2") (pinfunction "IOA_2") (pintype "passive"))
    )
    (net (code "33") (name "/SPI1_IOB") (class "Default")
      (node (ref "HF_CORE1") (pin "29") (pinfunction "PC4/ETH_RMII_RX_D0/ETH_MII_RX_D0/ADC12_IN14_29") (pintype "passive"))
      (node (ref "SPI") (pin "3") (pinfunction "IOB_3") (pintype "passive"))
    )
    (net (code "34") (name "/SPI1_MISO") (class "Default")
      (node (ref "HF_CORE1") (pin "27") (pinfunction "PA6/SPI1_MISO/TIM8_BKIN/TIM13_CH1/DCMI_PIXCLK/TIM3_CH1/TIM1_BKIN/ADC12_IN6_27") (pintype "passive"))
      (node (ref "SPI") (pin "6") (pinfunction "SPI_MISO_6") (pintype "passive"))
    )
    (net (code "35") (name "/SPI1_MOSI") (class "Default")
      (node (ref "HF_CORE1") (pin "28") (pinfunction "PA7/SPI1_MOSI/TIM8_CH1N/TIM14_CH1/TIM3_CH2/TIM1_CH1N/ADC12_IN7_28") (pintype "passive"))
      (node (ref "SPI") (pin "4") (pinfunction "SPI_MOSI_4") (pintype "passive"))
    )
    (net (code "36") (name "/SPI1_NSS") (class "Default")
      (node (ref "HF_CORE1") (pin "25") (pinfunction "PA4/SPI1_NSS/SPI3_NSS/USART2_CK/DCMI_HSYNC/OTG_HS_SOF/I2S3_WS/ADC12_IN4/DAC1_OUT_25") (pintype "passive"))
      (node (ref "SPI") (pin "8") (pinfunction "SPI_NSS_8") (pintype "passive"))
    )
    (net (code "37") (name "/SPI1_SCK") (class "Default")
      (node (ref "HF_CORE1") (pin "26") (pinfunction "PA5/SPI1_SCK/OTG_HS_ULPI_CK/TIM2_CH1_ETR/TIM8_CHIN/ADC12_IN5/DAC2_OUT_26") (pintype "passive"))
      (node (ref "SPI") (pin "7") (pinfunction "SPI_SCK_7") (pintype "passive"))
    )
    (net (code "38") (name "/SWCLK") (class "Default")
      (node (ref "HF_CORE1") (pin "71") (pinfunction "PA14/JTCK/SWCLK/EVENTOUT_71") (pintype "passive"))
      (node (ref "R20") (pin "2") (pinfunction "2_2") (pintype "passive"))
      (node (ref "SWD") (pin "3") (pinfunction "SWCLK_3") (pintype "passive"))
    )
    (net (code "39") (name "/SWDIO") (class "Default")
      (node (ref "HF_CORE1") (pin "70") (pinfunction "PA13/JTMS/SWDIO/EVENTOUT_70") (pintype "passive"))
      (node (ref "R21") (pin "2") (pinfunction "2_2") (pintype "passive"))
      (node (ref "SWD") (pin "4") (pinfunction "SWDIO_4") (pintype "passive"))
    )
    (net (code "40") (name "/TIM1_PWMOUT1") (class "Default")
      (node (ref "R25") (pin "2") (pinfunction "2_2") (pintype "passive"))
      (node (ref "SERVO1") (pin "10") (pinfunction "10_10") (pintype "passive"))
      (node (ref "motor1") (pin "2") (pinfunction "PWM_A_2") (pintype "passive"))
    )
    (net (code "41") (name "/TIM1_PWMOUT2") (class "Default")
      (node (ref "R26") (pin "2") (pinfunction "2_2") (pintype "passive"))
      (node (ref "SERVO1") (pin "7") (pinfunction "7_7") (pintype "passive"))
      (node (ref "motor1") (pin "3") (pinfunction "PWM_B_3") (pintype "passive"))
    )
    (net (code "42") (name "/TIM1_PWMOUT3") (class "Default")
      (node (ref "R28") (pin "2") (pinfunction "2_2") (pintype "passive"))
      (node (ref "SERVO1") (pin "4") (pinfunction "4_4") (pintype "passive"))
      (node (ref "motor2") (pin "2") (pinfunction "PWM_A_2") (pintype "passive"))
    )
    (net (code "43") (name "/TIM1_PWMOUT4") (class "Default")
      (node (ref "R29") (pin "2") (pinfunction "2_2") (pintype "passive"))
      (node (ref "SERVO1") (pin "1") (pinfunction "1_1") (pintype "passive"))
      (node (ref "motor2") (pin "3") (pinfunction "PWM_B_3") (pintype "passive"))
    )
    (net (code "44") (name "/TIM2_ENCODR1_A") (class "Default")
      (node (ref "C20") (pin "2") (pintype "passive"))
      (node (ref "HF_CORE1") (pin "72") (pinfunction "PA15/JTDI/SPI3_NSS/I2S3_WS/TIM2_CH1_ETR/SPI1_NSS/EVENTOUT_72") (pintype "passive"))
      (node (ref "motor1") (pin "7") (pinfunction "ENCODER_A_7") (pintype "passive"))
    )
    (net (code "45") (name "/TIM2_ENCODR1_B") (class "Default")
      (node (ref "C21") (pin "2") (pintype "passive"))
      (node (ref "HF_CORE1") (pin "84") (pinfunction "PB3/JTDO/TRACESWO/SPI3_SCK/I2S3_CK/TIM2_CH2/SPI1_SCK/EVENTOUT_84") (pintype "passive"))
      (node (ref "motor1") (pin "8") (pinfunction "ENCODER_B_8") (pintype "passive"))
    )
    (net (code "46") (name "/TIM3_ENCODR2_A") (class "Default")
      (node (ref "C23") (pin "2") (pintype "passive"))
      (node (ref "HF_CORE1") (pin "85") (pinfunction "PB4/NJTRST/SPI3_MISO/TIM3_CH1/SPI1_MISO/I2S3ext_SD/EVENTOUT_85") (pintype "passive"))
      (node (ref "motor2") (pin "7") (pinfunction "ENCODER_A_7") (pintype "passive"))
    )
    (net (code "47") (name "/TIM3_ENCODR2_B") (class "Default")
      (node (ref "C24") (pin "2") (pintype "passive"))
      (node (ref "HF_CORE1") (pin "86") (pinfunction "PB5/I2C1_SMBA/CAN2_RX/OTG_HS_ULPI_D7/TIM3_CH2/SPI1_MOSI/SPI3_MOSI/DCMI_D10/I2S3_SD_86") (pintype "passive"))
      (node (ref "motor2") (pin "8") (pinfunction "ENCODER_B_8") (pintype "passive"))
    )
    (net (code "48") (name "/TIM4_ENCODR3_A") (class "Default")
      (node (ref "C32") (pin "2") (pintype "passive"))
      (node (ref "HF_CORE1") (pin "54") (pinfunction "PD12/FSMC_ALE/FSMC_A17/TIM4_CH1/USART3_RTS/EVENTOUT_54") (pintype "passive"))
      (node (ref "motor3") (pin "7") (pinfunction "ENCODER_A_7") (pintype "passive"))
    )
    (net (code "49") (name "/TIM4_ENCODR3_B") (class "Default")
      (node (ref "C33") (pin "2") (pintype "passive"))
      (node (ref "HF_CORE1") (pin "55") (pinfunction "PD13/FSMC_A18/TIM4_CH2/EVENTOUT_55") (pintype "passive"))
      (node (ref "motor3") (pin "8") (pinfunction "ENCODER_B_8") (pintype "passive"))
    )
    (net (code "50") (name "/TIM5_ENCODR4_A") (class "Default")
      (node (ref "C29") (pin "2") (pintype "passive"))
      (node (ref "HF_CORE1") (pin "19") (pinfunction "PA0-WKUP/USART2_CTS/UART4_TX/TIM2_CH1_ETR/TIM5_CH1/TIM8_ETR/ADC123_IN0_19") (pintype "passive"))
      (node (ref "UART4") (pin "2") (pinfunction "TX_2") (pintype "passive"))
      (node (ref "motor4") (pin "7") (pinfunction "ENCODER_A_7") (pintype "passive"))
    )
    (net (code "51") (name "/TIM5_ENCODR4_B") (class "Default")
      (node (ref "C30") (pin "2") (pintype "passive"))
      (node (ref "HF_CORE1") (pin "20") (pinfunction "PA1/USART2_RTS/UART4_RX/ETH_RMII_REF_CLK/TIM5_CH2/TIM2_CH2/ADC123_IN1_20") (pintype "passive"))
      (node (ref "UART4") (pin "4") (pinfunction "RX_4") (pintype "passive"))
      (node (ref "motor4") (pin "8") (pinfunction "ENCODER_B_8") (pintype "passive"))
    )
    (net (code "52") (name "/TIM8_PWMOUT1") (class "Default")
      (node (ref "R23") (pin "1") (pinfunction "1_1") (pintype "passive"))
      (node (ref "SERVO2") (pin "4") (pinfunction "4_4") (pintype "passive"))
      (node (ref "UART6") (pin "2") (pinfunction "TX_2") (pintype "passive"))
    )
    (net (code "53") (name "/TIM8_PWMOUT2") (class "Default")
      (node (ref "R22") (pin "1") (pinfunction "1_1") (pintype "passive"))
      (node (ref "SERVO2") (pin "1") (pinfunction "1_1") (pintype "passive"))
      (node (ref "UART6") (pin "4") (pinfunction "RX_4") (pintype "passive"))
    )
    (net (code "54") (name "/TIM9_PWMOUT1") (class "Default")
      (node (ref "R18") (pin "2") (pinfunction "2_2") (pintype "passive"))
      (node (ref "SERVO2") (pin "10") (pinfunction "10_10") (pintype "passive"))
      (node (ref "motor3") (pin "2") (pinfunction "PWM_A_2") (pintype "passive"))
    )
    (net (code "55") (name "/TIM9_PWMOUT2") (class "Default")
      (node (ref "R19") (pin "2") (pinfunction "2_2") (pintype "passive"))
      (node (ref "SERVO2") (pin "7") (pinfunction "7_7") (pintype "passive"))
      (node (ref "motor3") (pin "3") (pinfunction "PWM_B_3") (pintype "passive"))
    )
    (net (code "56") (name "/TIM12_PWMOUT1") (class "Default")
      (node (ref "R32") (pin "1") (pinfunction "1_1") (pintype "passive"))
      (node (ref "SERVO3") (pin "10") (pinfunction "10_10") (pintype "passive"))
      (node (ref "motor4") (pin "2") (pinfunction "PWM_A_2") (pintype "passive"))
    )
    (net (code "57") (name "/TIM12_PWMOUT2") (class "Default")
      (node (ref "R30") (pin "1") (pinfunction "1_1") (pintype "passive"))
      (node (ref "SERVO3") (pin "7") (pinfunction "7_7") (pintype "passive"))
      (node (ref "motor4") (pin "3") (pinfunction "PWM_B_3") (pintype "passive"))
    )
    (net (code "58") (name "/USART2USB_D+") (class "Default")
      (node (ref "HF_CORE1") (pin "59") (pinfunction "D+_59") (pintype "passive"))
      (node (ref "R35") (pin "1") (pinfunction "1_1") (pintype "passive"))
    )
    (net (code "59") (name "/USART2USB_D-") (class "Default")
      (node (ref "HF_CORE1") (pin "58") (pinfunction "D-_58") (pintype "passive"))
      (node (ref "R36") (pin "1") (pinfunction "1_1") (pintype "passive"))
    )
    (net (code "60") (name "/USART2_RX") (class "Default")
      (node (ref "HF_CORE1") (pin "24") (pinfunction "PA3/USART2_RX/TIM5_CH4/TIM9_CH2/TIM2_CH4/OTG_HS_ULPI_D0/ADC123_IN3_24") (pintype "passive"))
      (node (ref "UART2") (pin "4") (pinfunction "RX_4") (pintype "passive"))
    )
    (net (code "61") (name "/USART2_TX") (class "Default")
      (node (ref "HF_CORE1") (pin "21") (pinfunction "PA2/USART2_TX/TIM5_CH3/TIM9_CH1/TIM2_CH3/ADC123_IN2_21") (pintype "passive"))
      (node (ref "UART2") (pin "2") (pinfunction "TX_2") (pintype "passive"))
    )
    (net (code "62") (name "/USART3_RX") (class "Default")
      (node (ref "GPS") (pin "4") (pinfunction "RX_4") (pintype "passive"))
      (node (ref "HF_CORE1") (pin "51") (pinfunction "PD9/FSMC_D14/USART3_RX/EVENTOUT_51") (pintype "passive"))
      (node (ref "R41") (pin "1") (pinfunction "1_1") (pintype "passive"))
    )
    (net (code "63") (name "/USART3_TX") (class "Default")
      (node (ref "GPS") (pin "5") (pinfunction "TX_5") (pintype "passive"))
      (node (ref "HF_CORE1") (pin "50") (pinfunction "PD8/FSMC_D13/USART3_TX/EVENTOUT_50") (pintype "passive"))
      (node (ref "R37") (pin "2") (pinfunction "2_2") (pintype "passive"))
    )
    (net (code "64") (name "/USB_D+") (class "Default")
      (node (ref "HF_CORE1") (pin "69") (pinfunction "PA12/USART1_RTS/CAN1_TX/TIM1_ETR/OTG_FS_DP/EVENTOUT_69") (pintype "passive"))
      (node (ref "R40") (pin "1") (pinfunction "1_1") (pintype "passive"))
    )
    (net (code "65") (name "/USB_D-") (class "Default")
      (node (ref "HF_CORE1") (pin "65") (pinfunction "PA11/USART1_CTS/CAN1_RX/TIM1_CH4/OTG_FS_DM/EVENTOUT_65") (pintype "passive"))
      (node (ref "R42") (pin "1") (pinfunction "1_1") (pintype "passive"))
    )
    (net (code "66") (name "GND_Chip") (class "Default")
      (node (ref "AX1") (pin "7") (pinfunction "GND_7") (pintype "passive"))
      (node (ref "C1") (pin "1") (pinfunction "1_1") (pintype "passive"))
      (node (ref "C10") (pin "2") (pinfunction "2_2") (pintype "passive"))
      (node (ref "C13") (pin "1") (pintype "passive"))
      (node (ref "C16") (pin "2") (pintype "passive"))
      (node (ref "C17") (pin "2") (pintype "passive"))
      (node (ref "C18") (pin "2") (pintype "passive"))
      (node (ref "C19") (pin "1") (pintype "passive"))
      (node (ref "C20") (pin "1") (pintype "passive"))
      (node (ref "C21") (pin "1") (pintype "passive"))
      (node (ref "C22") (pin "1") (pintype "passive"))
      (node (ref "C23") (pin "1") (pintype "passive"))
      (node (ref "C24") (pin "1") (pintype "passive"))
      (node (ref "C25") (pin "2") (pintype "passive"))
      (node (ref "C26") (pin "2") (pintype "passive"))
      (node (ref "C27") (pin "2") (pintype "passive"))
      (node (ref "C28") (pin "1") (pintype "passive"))
      (node (ref "C29") (pin "1") (pintype "passive"))
      (node (ref "C30") (pin "1") (pintype "passive"))
      (node (ref "C31") (pin "1") (pintype "passive"))
      (node (ref "C32") (pin "1") (pintype "passive"))
      (node (ref "C33") (pin "1") (pintype "passive"))
      (node (ref "C7") (pin "2") (pintype "passive"))
      (node (ref "C8") (pin "1") (pinfunction "1_1") (pintype "passive"))
      (node (ref "C9") (pin "2") (pinfunction "2_2") (pintype "passive"))
      (node (ref "CAN") (pin "1") (pinfunction "GND_1") (pintype "passive"))
      (node (ref "CAN") (pin "5") (pinfunction "GND_5") (pintype "passive"))
      (node (ref "CAN") (pin "6") (pinfunction "LBase_6") (pintype "passive"))
      (node (ref "CAN") (pin "7") (pinfunction "RBase_7") (pintype "passive"))
      (node (ref "DSERVO") (pin "3") (pinfunction "3_3") (pintype "passive"))
      (node (ref "EC1") (pin "2") (pintype "passive"))
      (node (ref "GPS") (pin "1") (pinfunction "GND_1") (pintype "passive"))
      (node (ref "GPS") (pin "7") (pinfunction "LBase_7") (pintype "passive"))
      (node (ref "GPS") (pin "8") (pinfunction "RBase_8") (pintype "passive"))
      (node (ref "HF_CORE1") (pin "1") (pinfunction "GND_1") (pintype "passive"))
      (node (ref "HF_CORE1") (pin "22") (pinfunction "GND_22") (pintype "passive"))
      (node (ref "HF_CORE1") (pin "33") (pinfunction "PB2-BOOT1/EVENTOUT_33") (pintype "passive"))
      (node (ref "HF_CORE1") (pin "67") (pinfunction "GND_67") (pintype "passive"))
      (node (ref "HF_CORE1") (pin "68") (pinfunction "GND_68") (pintype "passive"))
      (node (ref "HF_CORE1") (pin "87") (pinfunction "BOOT0_87") (pintype "passive"))
      (node (ref "IIC") (pin "1") (pinfunction "GND_1") (pintype "passive"))
      (node (ref "IIC") (pin "5") (pinfunction "GND_5") (pintype "passive"))
      (node (ref "IIC") (pin "6") (pinfunction "LBase_6") (pintype "passive"))
      (node (ref "IIC") (pin "7") (pinfunction "RBase_7") (pintype "passive"))
      (node (ref "LED4") (pin "2") (pinfunction "K_2") (pintype "passive"))
      (node (ref "NM1") (pin "2") (pinfunction "S_2") (pintype "passive"))
      (node (ref "NM2") (pin "2") (pinfunction "S_2") (pintype "passive"))
      (node (ref "R16") (pin "1") (pinfunction "1_1") (pintype "passive"))
      (node (ref "R44") (pin "2") (pinfunction "2_2") (pintype "passive"))
      (node (ref "R46") (pin "2") (pinfunction "2_2") (pintype "passive"))
      (node (ref "R5") (pin "2") (pinfunction "2_2") (pintype "passive"))
      (node (ref "SERVO1") (pin "12") (pinfunction "12_12") (pintype "passive"))
      (node (ref "SERVO1") (pin "3") (pinfunction "3_3") (pintype "passive"))
      (node (ref "SERVO1") (pin "6") (pinfunction "6_6") (pintype "passive"))
      (node (ref "SERVO1") (pin "9") (pinfunction "9_9") (pintype "passive"))
      (node (ref "SERVO2") (pin "12") (pinfunction "12_12") (pintype "passive"))
      (node (ref "SERVO2") (pin "3") (pinfunction "3_3") (pintype "passive"))
      (node (ref "SERVO2") (pin "6") (pinfunction "6_6") (pintype "passive"))
      (node (ref "SERVO2") (pin "9") (pinfunction "9_9") (pintype "passive"))
      (node (ref "SERVO3") (pin "12") (pinfunction "12_12") (pintype "passive"))
      (node (ref "SERVO3") (pin "3") (pinfunction "3_3") (pintype "passive"))
      (node (ref "SERVO3") (pin "6") (pinfunction "6_6") (pintype "passive"))
      (node (ref "SERVO3") (pin "9") (pinfunction "9_9") (pintype "passive"))
      (node (ref "SPI") (pin "1") (pinfunction "GND_1") (pintype "passive"))
      (node (ref "SPI") (pin "10") (pinfunction "LBase_10") (pintype "passive"))
      (node (ref "SPI") (pin "11") (pinfunction "RBase_11") (pintype "passive"))
      (node (ref "SPI") (pin "9") (pinfunction "GND_9") (pintype "passive"))
      (node (ref "SWD") (pin "2") (pinfunction "GND_2") (pintype "passive"))
      (node (ref "SWD") (pin "5") (pinfunction "LBase_5") (pintype "passive"))
      (node (ref "SWD") (pin "6") (pinfunction "RBase_6") (pintype "passive"))
      (node (ref "TF1") (pin "10") (pinfunction "GND_10") (pintype "passive"))
      (node (ref "TF1") (pin "11") (pinfunction "GND_11") (pintype "passive"))
      (node (ref "TF1") (pin "12") (pinfunction "GND_12") (pintype "passive"))
      (node (ref "TF1") (pin "13") (pinfunction "GND_13") (pintype "passive"))
      (node (ref "TF1") (pin "6") (pinfunction "GND_6") (pintype "passive"))
      (node (ref "TF1") (pin "9") (pinfunction "GND_9") (pintype "passive"))
      (node (ref "U1") (pin "3") (pinfunction "Vout-_3") (pintype "passive"))
      (node (ref "U1") (pin "4") (pinfunction "Vout-_4") (pintype "passive"))
      (node (ref "U1") (pin "5") (pinfunction "Vin-_5") (pintype "passive"))
      (node (ref "U1") (pin "6") (pinfunction "Vin-_6") (pintype "passive"))
      (node (ref "U2") (pin "2") (pinfunction "GND_2") (pintype "passive"))
      (node (ref "UART2") (pin "1") (pinfunction "GND_1") (pintype "passive"))
      (node (ref "UART2") (pin "5") (pinfunction "GND_5") (pintype "passive"))
      (node (ref "UART2") (pin "6") (pinfunction "LBase_6") (pintype "passive"))
      (node (ref "UART2") (pin "7") (pinfunction "RBase_7") (pintype "passive"))
      (node (ref "UART4") (pin "1") (pinfunction "GND_1") (pintype "passive"))
      (node (ref "UART4") (pin "5") (pinfunction "GND_5") (pintype "passive"))
      (node (ref "UART4") (pin "6") (pinfunction "LBase_6") (pintype "passive"))
      (node (ref "UART4") (pin "7") (pinfunction "RBase_7") (pintype "passive"))
      (node (ref "UART6") (pin "1") (pinfunction "GND_1") (pintype "passive"))
      (node (ref "UART6") (pin "5") (pinfunction "GND_5") (pintype "passive"))
      (node (ref "UART6") (pin "6") (pinfunction "LBase_6") (pintype "passive"))
      (node (ref "UART6") (pin "7") (pinfunction "RBase_7") (pintype "passive"))
      (node (ref "USB1") (pin "5") (pinfunction "GND_5") (pintype "passive"))
      (node (ref "USB2") (pin "5") (pinfunction "GND_5") (pintype "passive"))
      (node (ref "VP1") (pin "2") (pinfunction "GND_2") (pintype "passive"))
      (node (ref "VP1") (pin "8") (pinfunction "STB_8") (pintype "passive"))
      (node (ref "motor1") (pin "1") (pinfunction "GND_1") (pintype "passive"))
      (node (ref "motor1") (pin "10") (pinfunction "LBase_10") (pintype "passive"))
      (node (ref "motor1") (pin "11") (pinfunction "RBase_11") (pintype "passive"))
      (node (ref "motor1") (pin "9") (pinfunction "GND_9") (pintype "passive"))
      (node (ref "motor2") (pin "1") (pinfunction "GND_1") (pintype "passive"))
      (node (ref "motor2") (pin "10") (pinfunction "LBase_10") (pintype "passive"))
      (node (ref "motor2") (pin "11") (pinfunction "RBase_11") (pintype "passive"))
      (node (ref "motor2") (pin "9") (pinfunction "GND_9") (pintype "passive"))
      (node (ref "motor3") (pin "1") (pinfunction "GND_1") (pintype "passive"))
      (node (ref "motor3") (pin "10") (pinfunction "LBase_10") (pintype "passive"))
      (node (ref "motor3") (pin "11") (pinfunction "RBase_11") (pintype "passive"))
      (node (ref "motor3") (pin "9") (pinfunction "GND_9") (pintype "passive"))
      (node (ref "motor4") (pin "1") (pinfunction "GND_1") (pintype "passive"))
      (node (ref "motor4") (pin "10") (pinfunction "LBase_10") (pintype "passive"))
      (node (ref "motor4") (pin "11") (pinfunction "RBase_11") (pintype "passive"))
      (node (ref "motor4") (pin "9") (pinfunction "GND_9") (pintype "passive"))
      (node (ref "power1") (pin "2") (pinfunction "-_2") (pintype "passive"))
      (node (ref "rst1") (pin "1") (pintype "passive"))
    )
    (net (code "67") (name "Net-(AX1-1A)") (class "Default")
      (node (ref "AX1") (pin "2") (pinfunction "1A_2") (pintype "passive"))
      (node (ref "R37") (pin "1") (pinfunction "1_1") (pintype "passive"))
    )
    (net (code "68") (name "Net-(AX1-2Y)") (class "Default")
      (node (ref "AX1") (pin "6") (pinfunction "2Y_6") (pintype "passive"))
      (node (ref "R41") (pin "2") (pinfunction "2_2") (pintype "passive"))
    )
    (net (code "69") (name "Net-(AX1-3A)") (class "Default")
      (node (ref "AX1") (pin "9") (pinfunction "3A_9") (pintype "passive"))
      (node (ref "R44") (pin "1") (pinfunction "1_1") (pintype "passive"))
    )
    (net (code "70") (name "Net-(B1-+)") (class "Default")
      (node (ref "B1") (pin "1") (pinfunction "+_1") (pintype "passive"))
      (node (ref "R13") (pin "2") (pinfunction "2_2") (pintype "passive"))
    )
    (net (code "71") (name "Net-(B1--)") (class "Default")
      (node (ref "B1") (pin "2") (pinfunction "-_2") (pintype "passive"))
      (node (ref "NM1") (pin "3") (pinfunction "D_3") (pintype "passive"))
    )
    (net (code "72") (name "Net-(D1-Pad2)") (class "Default")
      (node (ref "D1") (pin "2") (pintype "passive"))
      (node (ref "U1") (pin "7") (pinfunction "Vin+_7") (pintype "passive"))
      (node (ref "U1") (pin "8") (pinfunction "Vin+_8") (pintype "passive"))
    )
    (net (code "73") (name "Net-(D2-Pad1)") (class "Default")
      (node (ref "D2") (pin "1") (pintype "passive"))
      (node (ref "U1") (pin "1") (pinfunction "Vout+_1") (pintype "passive"))
      (node (ref "U1") (pin "2") (pinfunction "Vout+_2") (pintype "passive"))
    )
    (net (code "74") (name "Net-(D2-Pad2)") (class "Default")
      (node (ref "D2") (pin "2") (pintype "passive"))
      (node (ref "f1") (pin "1") (pintype "passive"))
    )
    (net (code "75") (name "Net-(HF_CORE1-PB14{slash}SPI2_MISO{slash}TIM1_CH2N{slash}TIM12_CH1{slash}OTG_HS_DM{slash}USART3_RTS{slash}TIM8_CH2N{slash}I2S2ext_SD{slash}EVENTOUT)") (class "Default")
      (node (ref "HF_CORE1") (pin "47") (pinfunction "PB14/SPI2_MISO/TIM1_CH2N/TIM12_CH1/OTG_HS_DM/USART3_RTS/TIM8_CH2N/I2S2ext_SD/EVENTOUT_47") (pintype "passive"))
      (node (ref "R32") (pin "2") (pinfunction "2_2") (pintype "passive"))
    )
    (net (code "76") (name "Net-(HF_CORE1-PB15{slash}SPI2_MOSI{slash}I2S2_SD{slash}TIM1_CH3N{slash}TIM8_CH3N{slash}TIM12_CH2{slash}OTG_HS_DP{slash}EVENTOUT)") (class "Default")
      (node (ref "HF_CORE1") (pin "48") (pinfunction "PB15/SPI2_MOSI/I2S2_SD/TIM1_CH3N/TIM8_CH3N/TIM12_CH2/OTG_HS_DP/EVENTOUT_48") (pintype "passive"))
      (node (ref "R30") (pin "2") (pinfunction "2_2") (pintype "passive"))
    )
    (net (code "77") (name "Net-(HF_CORE1-PC6{slash}I2S2_MCK{slash}TIM8_CH1{slash}SDIO_D6{slash}USART6_TX{slash}DCMI_D0{slash}TIM3_CH1{slash}EVENTOUT)") (class "Default")
      (node (ref "HF_CORE1") (pin "60") (pinfunction "PC6/I2S2_MCK/TIM8_CH1/SDIO_D6/USART6_TX/DCMI_D0/TIM3_CH1/EVENTOUT_60") (pintype "passive"))
      (node (ref "R23") (pin "2") (pinfunction "2_2") (pintype "passive"))
    )
    (net (code "78") (name "Net-(HF_CORE1-PC7{slash}I2S3_MCK{slash}TIM8_CH2{slash}SDIO_D7{slash}USART6_RX{slash}DCMI_D1{slash}TIM3_CH2{slash}EVENTOUT)") (class "Default")
      (node (ref "HF_CORE1") (pin "61") (pinfunction "PC7/I2S3_MCK/TIM8_CH2/SDIO_D7/USART6_RX/DCMI_D1/TIM3_CH2/EVENTOUT_61") (pintype "passive"))
      (node (ref "R22") (pin "2") (pinfunction "2_2") (pintype "passive"))
    )
    (net (code "79") (name "Net-(HF_CORE1-PE4{slash}TRACED1{slash}FSMC_A20{slash}DCMI_D4{slash}EVENT_OUT)") (class "Default")
      (node (ref "HF_CORE1") (pin "7") (pinfunction "PE4/TRACED1/FSMC_A20/DCMI_D4/EVENT_OUT_7") (pintype "passive"))
      (node (ref "R17") (pin "1") (pinfunction "1_1") (pintype "passive"))
    )
    (net (code "80") (name "Net-(HF_CORE1-PE5{slash}TRACED2{slash}FSMC_A21{slash}TIM9_CH1{slash}DCMI_D6{slash}EVENTOUT)") (class "Default")
      (node (ref "HF_CORE1") (pin "8") (pinfunction "PE5/TRACED2/FSMC_A21/TIM9_CH1/DCMI_D6/EVENTOUT_8") (pintype "passive"))
      (node (ref "R18") (pin "1") (pinfunction "1_1") (pintype "passive"))
    )
    (net (code "81") (name "Net-(HF_CORE1-PE6{slash}TRACED3{slash}FSMC_A22{slash}TIM9_CH2{slash}DCMI_D7{slash}EVENTOUT)") (class "Default")
      (node (ref "HF_CORE1") (pin "9") (pinfunction "PE6/TRACED3/FSMC_A22/TIM9_CH2/DCMI_D7/EVENTOUT_9") (pintype "passive"))
      (node (ref "R19") (pin "1") (pinfunction "1_1") (pintype "passive"))
    )
    (net (code "82") (name "Net-(HF_CORE1-PE8{slash}FSMC_D5{slash}TIM1_CH1IN{slash}EVENTOUT)") (class "Default")
      (node (ref "HF_CORE1") (pin "35") (pinfunction "PE8/FSMC_D5/TIM1_CH1IN/EVENTOUT_35") (pintype "passive"))
      (node (ref "R24") (pin "1") (pinfunction "1_1") (pintype "passive"))
    )
    (net (code "83") (name "Net-(HF_CORE1-PE9{slash}FSMC_D6{slash}TIM1_CH1{slash}EVENTOUT)") (class "Default")
      (node (ref "HF_CORE1") (pin "36") (pinfunction "PE9/FSMC_D6/TIM1_CH1/EVENTOUT_36") (pintype "passive"))
      (node (ref "R25") (pin "1") (pinfunction "1_1") (pintype "passive"))
    )
    (net (code "84") (name "Net-(HF_CORE1-PE11{slash}FSMC_D8{slash}TIM1_CH2{slash}EVENTOUT)") (class "Default")
      (node (ref "HF_CORE1") (pin "38") (pinfunction "PE11/FSMC_D8/TIM1_CH2/EVENTOUT_38") (pintype "passive"))
      (node (ref "R26") (pin "1") (pinfunction "1_1") (pintype "passive"))
    )
    (net (code "85") (name "Net-(HF_CORE1-PE12{slash}FSMC_D9{slash}TIM1_CH3N{slash}EVENTOUT)") (class "Default")
      (node (ref "HF_CORE1") (pin "39") (pinfunction "PE12/FSMC_D9/TIM1_CH3N/EVENTOUT_39") (pintype "passive"))
      (node (ref "R27") (pin "1") (pinfunction "1_1") (pintype "passive"))
    )
    (net (code "86") (name "Net-(HF_CORE1-PE13{slash}FSMC_D10{slash}TIM1_CH3{slash}EVENTOUT)") (class "Default")
      (node (ref "HF_CORE1") (pin "40") (pinfunction "PE13/FSMC_D10/TIM1_CH3/EVENTOUT_40") (pintype "passive"))
      (node (ref "R28") (pin "1") (pinfunction "1_1") (pintype "passive"))
    )
    (net (code "87") (name "Net-(HF_CORE1-PE14{slash}FSMC_D11{slash}TIM1_CH4{slash}EVENT)") (class "Default")
      (node (ref "HF_CORE1") (pin "41") (pinfunction "PE14/FSMC_D11/TIM1_CH4/EVENT_41") (pintype "passive"))
      (node (ref "R29") (pin "1") (pinfunction "1_1") (pintype "passive"))
    )
    (net (code "88") (name "Net-(HF_CORE1-PE15{slash}FSMC_D12{slash}TIM1_BKIN{slash}EVENTOUT)") (class "Default")
      (node (ref "HF_CORE1") (pin "42") (pinfunction "PE15/FSMC_D12/TIM1_BKIN/EVENTOUT_42") (pintype "passive"))
      (node (ref "R31") (pin "1") (pinfunction "1_1") (pintype "passive"))
    )
    (net (code "89") (name "Net-(LED1-Pad1)") (class "Default")
      (node (ref "LED1") (pin "1") (pintype "passive"))
      (node (ref "R1") (pin "2") (pinfunction "2_2") (pintype "passive"))
    )
    (net (code "90") (name "Net-(LED2-Pad1)") (class "Default")
      (node (ref "LED2") (pin "1") (pintype "passive"))
      (node (ref "R3") (pin "2") (pinfunction "2_2") (pintype "passive"))
    )
    (net (code "91") (name "Net-(LED3-Pad1)") (class "Default")
      (node (ref "LED3") (pin "1") (pintype "passive"))
      (node (ref "R8") (pin "2") (pinfunction "2_2") (pintype "passive"))
    )
    (net (code "92") (name "Net-(LED4-A)") (class "Default")
      (node (ref "LED4") (pin "1") (pinfunction "A_1") (pintype "passive"))
      (node (ref "R7") (pin "2") (pinfunction "2_2") (pintype "passive"))
    )
    (net (code "93") (name "Net-(NM1-G)") (class "Default")
      (node (ref "NM1") (pin "1") (pinfunction "G_1") (pintype "passive"))
      (node (ref "R15") (pin "1") (pinfunction "1_1") (pintype "passive"))
      (node (ref "R16") (pin "2") (pinfunction "2_2") (pintype "passive"))
    )
    (net (code "94") (name "Net-(NM2-G)") (class "Default")
      (node (ref "NM2") (pin "1") (pinfunction "G_1") (pintype "passive"))
      (node (ref "SERVO3") (pin "1") (pinfunction "1_1") (pintype "passive"))
    )
    (net (code "95") (name "Net-(U2-BP)") (class "Default")
      (node (ref "C8") (pin "2") (pinfunction "2_2") (pintype "passive"))
      (node (ref "U2") (pin "4") (pinfunction "BP_4") (pintype "passive"))
    )
    (net (code "96") (name "Net-(U2-EN)") (class "Default")
      (node (ref "R10") (pin "2") (pinfunction "2_2") (pintype "passive"))
      (node (ref "U2") (pin "3") (pinfunction "EN_3") (pintype "passive"))
    )
    (net (code "97") (name "Net-(USB1-D+)") (class "Default")
      (node (ref "R35") (pin "2") (pinfunction "2_2") (pintype "passive"))
      (node (ref "USB1") (pin "3") (pinfunction "D+_3") (pintype "passive"))
    )
    (net (code "98") (name "Net-(USB1-D-)") (class "Default")
      (node (ref "R36") (pin "2") (pinfunction "2_2") (pintype "passive"))
      (node (ref "USB1") (pin "2") (pinfunction "D-_2") (pintype "passive"))
    )
    (net (code "99") (name "Net-(USB1-VCC)") (class "Default")
      (node (ref "USB1") (pin "1") (pinfunction "VCC_1") (pintype "passive"))
      (node (ref "f2") (pin "1") (pintype "passive"))
    )
    (net (code "100") (name "Net-(USB2-D+)") (class "Default")
      (node (ref "R40") (pin "2") (pinfunction "2_2") (pintype "passive"))
      (node (ref "USB2") (pin "3") (pinfunction "D+_3") (pintype "passive"))
    )
    (net (code "101") (name "Net-(USB2-D-)") (class "Default")
      (node (ref "R42") (pin "2") (pinfunction "2_2") (pintype "passive"))
      (node (ref "USB2") (pin "2") (pinfunction "D-_2") (pintype "passive"))
    )
    (net (code "102") (name "Net-(USB2-VCC)") (class "Default")
      (node (ref "USB2") (pin "1") (pinfunction "VCC_1") (pintype "passive"))
      (node (ref "f3") (pin "1") (pintype "passive"))
    )
    (net (code "103") (name "Net-(VP1-SPLIT)") (class "Default")
      (node (ref "R45") (pin "1") (pinfunction "1_1") (pintype "passive"))
      (node (ref "R46") (pin "1") (pinfunction "1_1") (pintype "passive"))
      (node (ref "VP1") (pin "5") (pinfunction "SPLIT_5") (pintype "passive"))
    )
    (net (code "104") (name "VCC3.3V_Chip") (class "Default")
      (node (ref "C10") (pin "1") (pinfunction "1_1") (pintype "passive"))
      (node (ref "C13") (pin "2") (pintype "passive"))
      (node (ref "C9") (pin "1") (pinfunction "1_1") (pintype "passive"))
      (node (ref "R11") (pin "2") (pinfunction "2_2") (pintype "passive"))
      (node (ref "R12") (pin "2") (pinfunction "2_2") (pintype "passive"))
      (node (ref "R33") (pin "2") (pinfunction "2_2") (pintype "passive"))
      (node (ref "R34") (pin "2") (pinfunction "2_2") (pintype "passive"))
      (node (ref "R4") (pin "2") (pinfunction "2_2") (pintype "passive"))
      (node (ref "R45") (pin "2") (pinfunction "2_2") (pintype "passive"))
      (node (ref "R6") (pin "2") (pinfunction "2_2") (pintype "passive"))
      (node (ref "R7") (pin "1") (pinfunction "1_1") (pintype "passive"))
      (node (ref "R9") (pin "2") (pinfunction "2_2") (pintype "passive"))
      (node (ref "TF1") (pin "4") (pinfunction "VCC3.3V_4") (pintype "passive"))
      (node (ref "U2") (pin "5") (pinfunction "OUT_5") (pintype "passive"))
      (node (ref "VP1") (pin "3") (pinfunction "VCC_3") (pintype "passive"))
    )
    (net (code "105") (name "VCC3.3_OUT") (class "Default")
      (node (ref "HF_CORE1") (pin "5") (pinfunction "VCC3.3_OUT_5") (pintype "passive"))
      (node (ref "R14") (pin "1") (pinfunction "1_1") (pintype "passive"))
      (node (ref "R20") (pin "1") (pinfunction "1_1") (pintype "passive"))
      (node (ref "R21") (pin "1") (pinfunction "1_1") (pintype "passive"))
    )
    (net (code "106") (name "VCC5V_Chip") (class "Default")
      (node (ref "AX1") (pin "14") (pinfunction "VCC_14") (pintype "passive"))
      (node (ref "C1") (pin "2") (pinfunction "2_2") (pintype "passive"))
      (node (ref "C16") (pin "1") (pintype "passive"))
      (node (ref "C17") (pin "1") (pintype "passive"))
      (node (ref "C18") (pin "1") (pintype "passive"))
      (node (ref "C25") (pin "1") (pintype "passive"))
      (node (ref "C26") (pin "1") (pintype "passive"))
      (node (ref "C27") (pin "1") (pintype "passive"))
      (node (ref "CAN") (pin "3") (pinfunction "VCC5V_3") (pintype "passive"))
      (node (ref "D3") (pin "2") (pintype "passive"))
      (node (ref "GPS") (pin "6") (pinfunction "VCC5V_6") (pintype "passive"))
      (node (ref "HF_CORE1") (pin "23") (pinfunction "VCC_IN_23") (pintype "passive"))
      (node (ref "IIC") (pin "3") (pinfunction "VCC5V_3") (pintype "passive"))
      (node (ref "R1") (pin "1") (pinfunction "1_1") (pintype "passive"))
      (node (ref "R10") (pin "1") (pinfunction "1_1") (pintype "passive"))
      (node (ref "R13") (pin "1") (pinfunction "1_1") (pintype "passive"))
      (node (ref "R3") (pin "1") (pinfunction "1_1") (pintype "passive"))
      (node (ref "R38") (pin "1") (pinfunction "1_1") (pintype "passive"))
      (node (ref "R43") (pin "2") (pinfunction "2_2") (pintype "passive"))
      (node (ref "R47") (pin "1") (pinfunction "1_1") (pintype "passive"))
      (node (ref "R8") (pin "1") (pinfunction "1_1") (pintype "passive"))
      (node (ref "SERVO1") (pin "11") (pinfunction "11_11") (pintype "passive"))
      (node (ref "SERVO1") (pin "2") (pinfunction "2_2") (pintype "passive"))
      (node (ref "SERVO1") (pin "5") (pinfunction "5_5") (pintype "passive"))
      (node (ref "SERVO1") (pin "8") (pinfunction "8_8") (pintype "passive"))
      (node (ref "SERVO2") (pin "11") (pinfunction "11_11") (pintype "passive"))
      (node (ref "SERVO2") (pin "2") (pinfunction "2_2") (pintype "passive"))
      (node (ref "SERVO2") (pin "5") (pinfunction "5_5") (pintype "passive"))
      (node (ref "SERVO2") (pin "8") (pinfunction "8_8") (pintype "passive"))
      (node (ref "SERVO3") (pin "11") (pinfunction "11_11") (pintype "passive"))
      (node (ref "SERVO3") (pin "2") (pinfunction "2_2") (pintype "passive"))
      (node (ref "SERVO3") (pin "5") (pinfunction "5_5") (pintype "passive"))
      (node (ref "SERVO3") (pin "8") (pinfunction "8_8") (pintype "passive"))
      (node (ref "SPI") (pin "5") (pinfunction "VCC5V_5") (pintype "passive"))
      (node (ref "U2") (pin "1") (pinfunction "VIN_1") (pintype "passive"))
      (node (ref "UART2") (pin "3") (pinfunction "VCC5V_3") (pintype "passive"))
      (node (ref "UART4") (pin "3") (pinfunction "VCC5V_3") (pintype "passive"))
      (node (ref "UART6") (pin "3") (pinfunction "VCC5V_3") (pintype "passive"))
      (node (ref "f1") (pin "2") (pintype "passive"))
      (node (ref "motor1") (pin "5") (pinfunction "VCC5V_5") (pintype "passive"))
      (node (ref "motor2") (pin "5") (pinfunction "VCC5V_5") (pintype "passive"))
      (node (ref "motor3") (pin "5") (pinfunction "VCC5V_5") (pintype "passive"))
      (node (ref "motor4") (pin "5") (pinfunction "VCC5V_5") (pintype "passive"))
    )
    (net (code "107") (name "VCC_Battery") (class "Default")
      (node (ref "D1") (pin "1") (pintype "passive"))
      (node (ref "DSERVO") (pin "2") (pinfunction "2_2") (pintype "passive"))
      (node (ref "R2") (pin "1") (pinfunction "1_1") (pintype "passive"))
      (node (ref "power1") (pin "1") (pinfunction "+_1") (pintype "passive"))
    )
    (net (code "108") (name "VCC_USB5V") (class "Default")
      (node (ref "D3") (pin "1") (pintype "passive"))
      (node (ref "HF_CORE1") (pin "66") (pinfunction "VCC5_USB_IN_66") (pintype "passive"))
      (node (ref "f2") (pin "2") (pintype "passive"))
      (node (ref "f3") (pin "2") (pintype "passive"))
    )
    (net (code "109") (name "unconnected-(AX1-4A-Pad12)") (class "Default")
      (node (ref "AX1") (pin "12") (pinfunction "4A_12") (pintype "passive"))
    )
    (net (code "110") (name "unconnected-(AX1-4OE-Pad13)") (class "Default")
      (node (ref "AX1") (pin "13") (pinfunction "4OE_13") (pintype "passive"))
    )
    (net (code "111") (name "unconnected-(AX1-4Y-Pad11)") (class "Default")
      (node (ref "AX1") (pin "11") (pinfunction "4Y_11") (pintype "passive"))
    )
    (net (code "112") (name "unconnected-(HF_CORE1-PA8{slash}MCO1{slash}USART1_CK{slash}TIM1_CH1{slash}I2C3_SCL{slash}OTG_FS_SOF{slash}EVENTOUT-Pad64)") (class "Default")
      (node (ref "HF_CORE1") (pin "64") (pinfunction "PA8/MCO1/USART1_CK/TIM1_CH1/I2C3_SCL/OTG_FS_SOF/EVENTOUT_64") (pintype "passive"))
    )
    (net (code "113") (name "unconnected-(HF_CORE1-PB8{slash}TIM4_CH3{slash}SDIO_D4{slash}TIM10_CH1{slash}DCMI_D6{slash}ETH_MII_TXD3{slash}I2C1_SCL{slash}CAN1_RX{slash}EVENTOUT-Pad88)") (class "Default")
      (node (ref "HF_CORE1") (pin "88") (pinfunction "PB8/TIM4_CH3/SDIO_D4/TIM10_CH1/DCMI_D6/ETH_MII_TXD3/I2C1_SCL/CAN1_RX/EVENTOUT_88") (pintype "passive"))
    )
    (net (code "114") (name "unconnected-(HF_CORE1-PB9{slash}SPI2_NSS{slash}I2S2_WS{slash}TIM4_CH4{slash}TIM11_CH1{slash}SDIO_D5{slash}DCMI_D7{slash}I2C1_SDA{slash}CAN1_TX-Pad2)") (class "Default")
      (node (ref "HF_CORE1") (pin "2") (pinfunction "PB9/SPI2_NSS/I2S2_WS/TIM4_CH4/TIM11_CH1/SDIO_D5/DCMI_D7/I2C1_SDA/CAN1_TX_2") (pintype "passive"))
    )
    (net (code "115") (name "unconnected-(HF_CORE1-PC14-OSC32_IN{slash}EVENTOUT-Pad12)") (class "Default")
      (node (ref "HF_CORE1") (pin "12") (pinfunction "PC14-OSC32_IN/EVENTOUT_12") (pintype "passive"))
    )
    (net (code "116") (name "unconnected-(HF_CORE1-PC15-OSC32_OUT{slash}EVENTOUT-Pad13)") (class "Default")
      (node (ref "HF_CORE1") (pin "13") (pinfunction "PC15-OSC32_OUT/EVENTOUT_13") (pintype "passive"))
    )
    (net (code "117") (name "unconnected-(HF_CORE1-PD0{slash}FSMC_D2{slash}CAN1_RX{slash}EVENTOUT-Pad76)") (class "Default")
      (node (ref "HF_CORE1") (pin "76") (pinfunction "PD0/FSMC_D2/CAN1_RX/EVENTOUT_76") (pintype "passive"))
    )
    (net (code "118") (name "unconnected-(HF_CORE1-PD1{slash}FSMC_D3{slash}CAN1_TX{slash}EVENTOUT-Pad77)") (class "Default")
      (node (ref "HF_CORE1") (pin "77") (pinfunction "PD1/FSMC_D3/CAN1_TX/EVENTOUT_77") (pintype "passive"))
    )
    (net (code "119") (name "unconnected-(HF_CORE1-PD3{slash}FSMC_CLK{slash}USART2_CTS{slash}EVENTOUT-Pad79)") (class "Default")
      (node (ref "HF_CORE1") (pin "79") (pinfunction "PD3/FSMC_CLK/USART2_CTS/EVENTOUT_79") (pintype "passive"))
    )
    (net (code "120") (name "unconnected-(HF_CORE1-PD4{slash}FSMC_NOE{slash}USART2_RTS{slash}EVENTOUT-Pad80)") (class "Default")
      (node (ref "HF_CORE1") (pin "80") (pinfunction "PD4/FSMC_NOE/USART2_RTS/EVENTOUT_80") (pintype "passive"))
    )
    (net (code "121") (name "unconnected-(HF_CORE1-PD5{slash}FSMC_NWE{slash}USART2_TX{slash}EVENTOUT-Pad81)") (class "Default")
      (node (ref "HF_CORE1") (pin "81") (pinfunction "PD5/FSMC_NWE/USART2_TX/EVENTOUT_81") (pintype "passive"))
    )
    (net (code "122") (name "unconnected-(HF_CORE1-PD7{slash}USART2_CK{slash}FSMC_NE1{slash}FSMC_NCE2{slash}EVENTOUT-Pad83)") (class "Default")
      (node (ref "HF_CORE1") (pin "83") (pinfunction "PD7/USART2_CK/FSMC_NE1/FSMC_NCE2/EVENTOUT_83") (pintype "passive"))
    )
    (net (code "123") (name "unconnected-(HF_CORE1-PD11{slash}FSMC_CLE{slash}FSMC_A16{slash}USART3_CTS{slash}EVENTOUT-Pad53)") (class "Default")
      (node (ref "HF_CORE1") (pin "53") (pinfunction "PD11/FSMC_CLE/FSMC_A16/USART3_CTS/EVENTOUT_53") (pintype "passive"))
    )
    (net (code "124") (name "unconnected-(HF_CORE1-PD14{slash}FSMC_D0{slash}TIM4_CH3{slash}EVENTOUT-Pad56)") (class "Default")
      (node (ref "HF_CORE1") (pin "56") (pinfunction "PD14/FSMC_D0/TIM4_CH3/EVENTOUT_56") (pintype "passive"))
    )
    (net (code "125") (name "unconnected-(HF_CORE1-PD15{slash}FSMC_D1{slash}TIM4_CH4{slash}EVENTOUT-Pad57)") (class "Default")
      (node (ref "HF_CORE1") (pin "57") (pinfunction "PD15/FSMC_D1/TIM4_CH4/EVENTOUT_57") (pintype "passive"))
    )
    (net (code "126") (name "unconnected-(HF_CORE1-PE7{slash}FSMC_D4{slash}TIM1_ETR{slash}EVENTOUT-Pad34)") (class "Default")
      (node (ref "HF_CORE1") (pin "34") (pinfunction "PE7/FSMC_D4/TIM1_ETR/EVENTOUT_34") (pintype "passive"))
    )
    (net (code "127") (name "unconnected-(HF_CORE1-PE10{slash}FSMC_D7{slash}TIM1_CH2N{slash}EVENTOUT-Pad37)") (class "Default")
      (node (ref "HF_CORE1") (pin "37") (pinfunction "PE10/FSMC_D7/TIM1_CH2N/EVENTOUT_37") (pintype "passive"))
    )
    (net (code "128") (name "unconnected-(HF_CORE1-V-BAT-Pad10)") (class "Default")
      (node (ref "HF_CORE1") (pin "10") (pinfunction "V-BAT_10") (pintype "passive"))
    )
    (net (code "129") (name "unconnected-(HF_CORE1-VCC3.3_OUT-Pad49)") (class "Default")
      (node (ref "HF_CORE1") (pin "49") (pinfunction "VCC3.3_OUT_49") (pintype "passive+no_connect"))
    )
    (net (code "130") (name "unconnected-(SWD-VCC3.3V-Pad1)") (class "Default")
      (node (ref "SWD") (pin "1") (pinfunction "VCC3.3V_1") (pintype "passive"))
    )
    (net (code "131") (name "unconnected-(USB1-NC-Pad4)") (class "Default")
      (node (ref "USB1") (pin "4") (pinfunction "NC_4") (pintype "passive+no_connect"))
    )
    (net (code "132") (name "unconnected-(USB2-NC-Pad4)") (class "Default")
      (node (ref "USB2") (pin "4") (pinfunction "NC_4") (pintype "passive+no_connect"))
    )
  )
)
